# I2S_XLR_Adapter.net
KiCad netlist of a schematic drawn in EasyEDA Pro
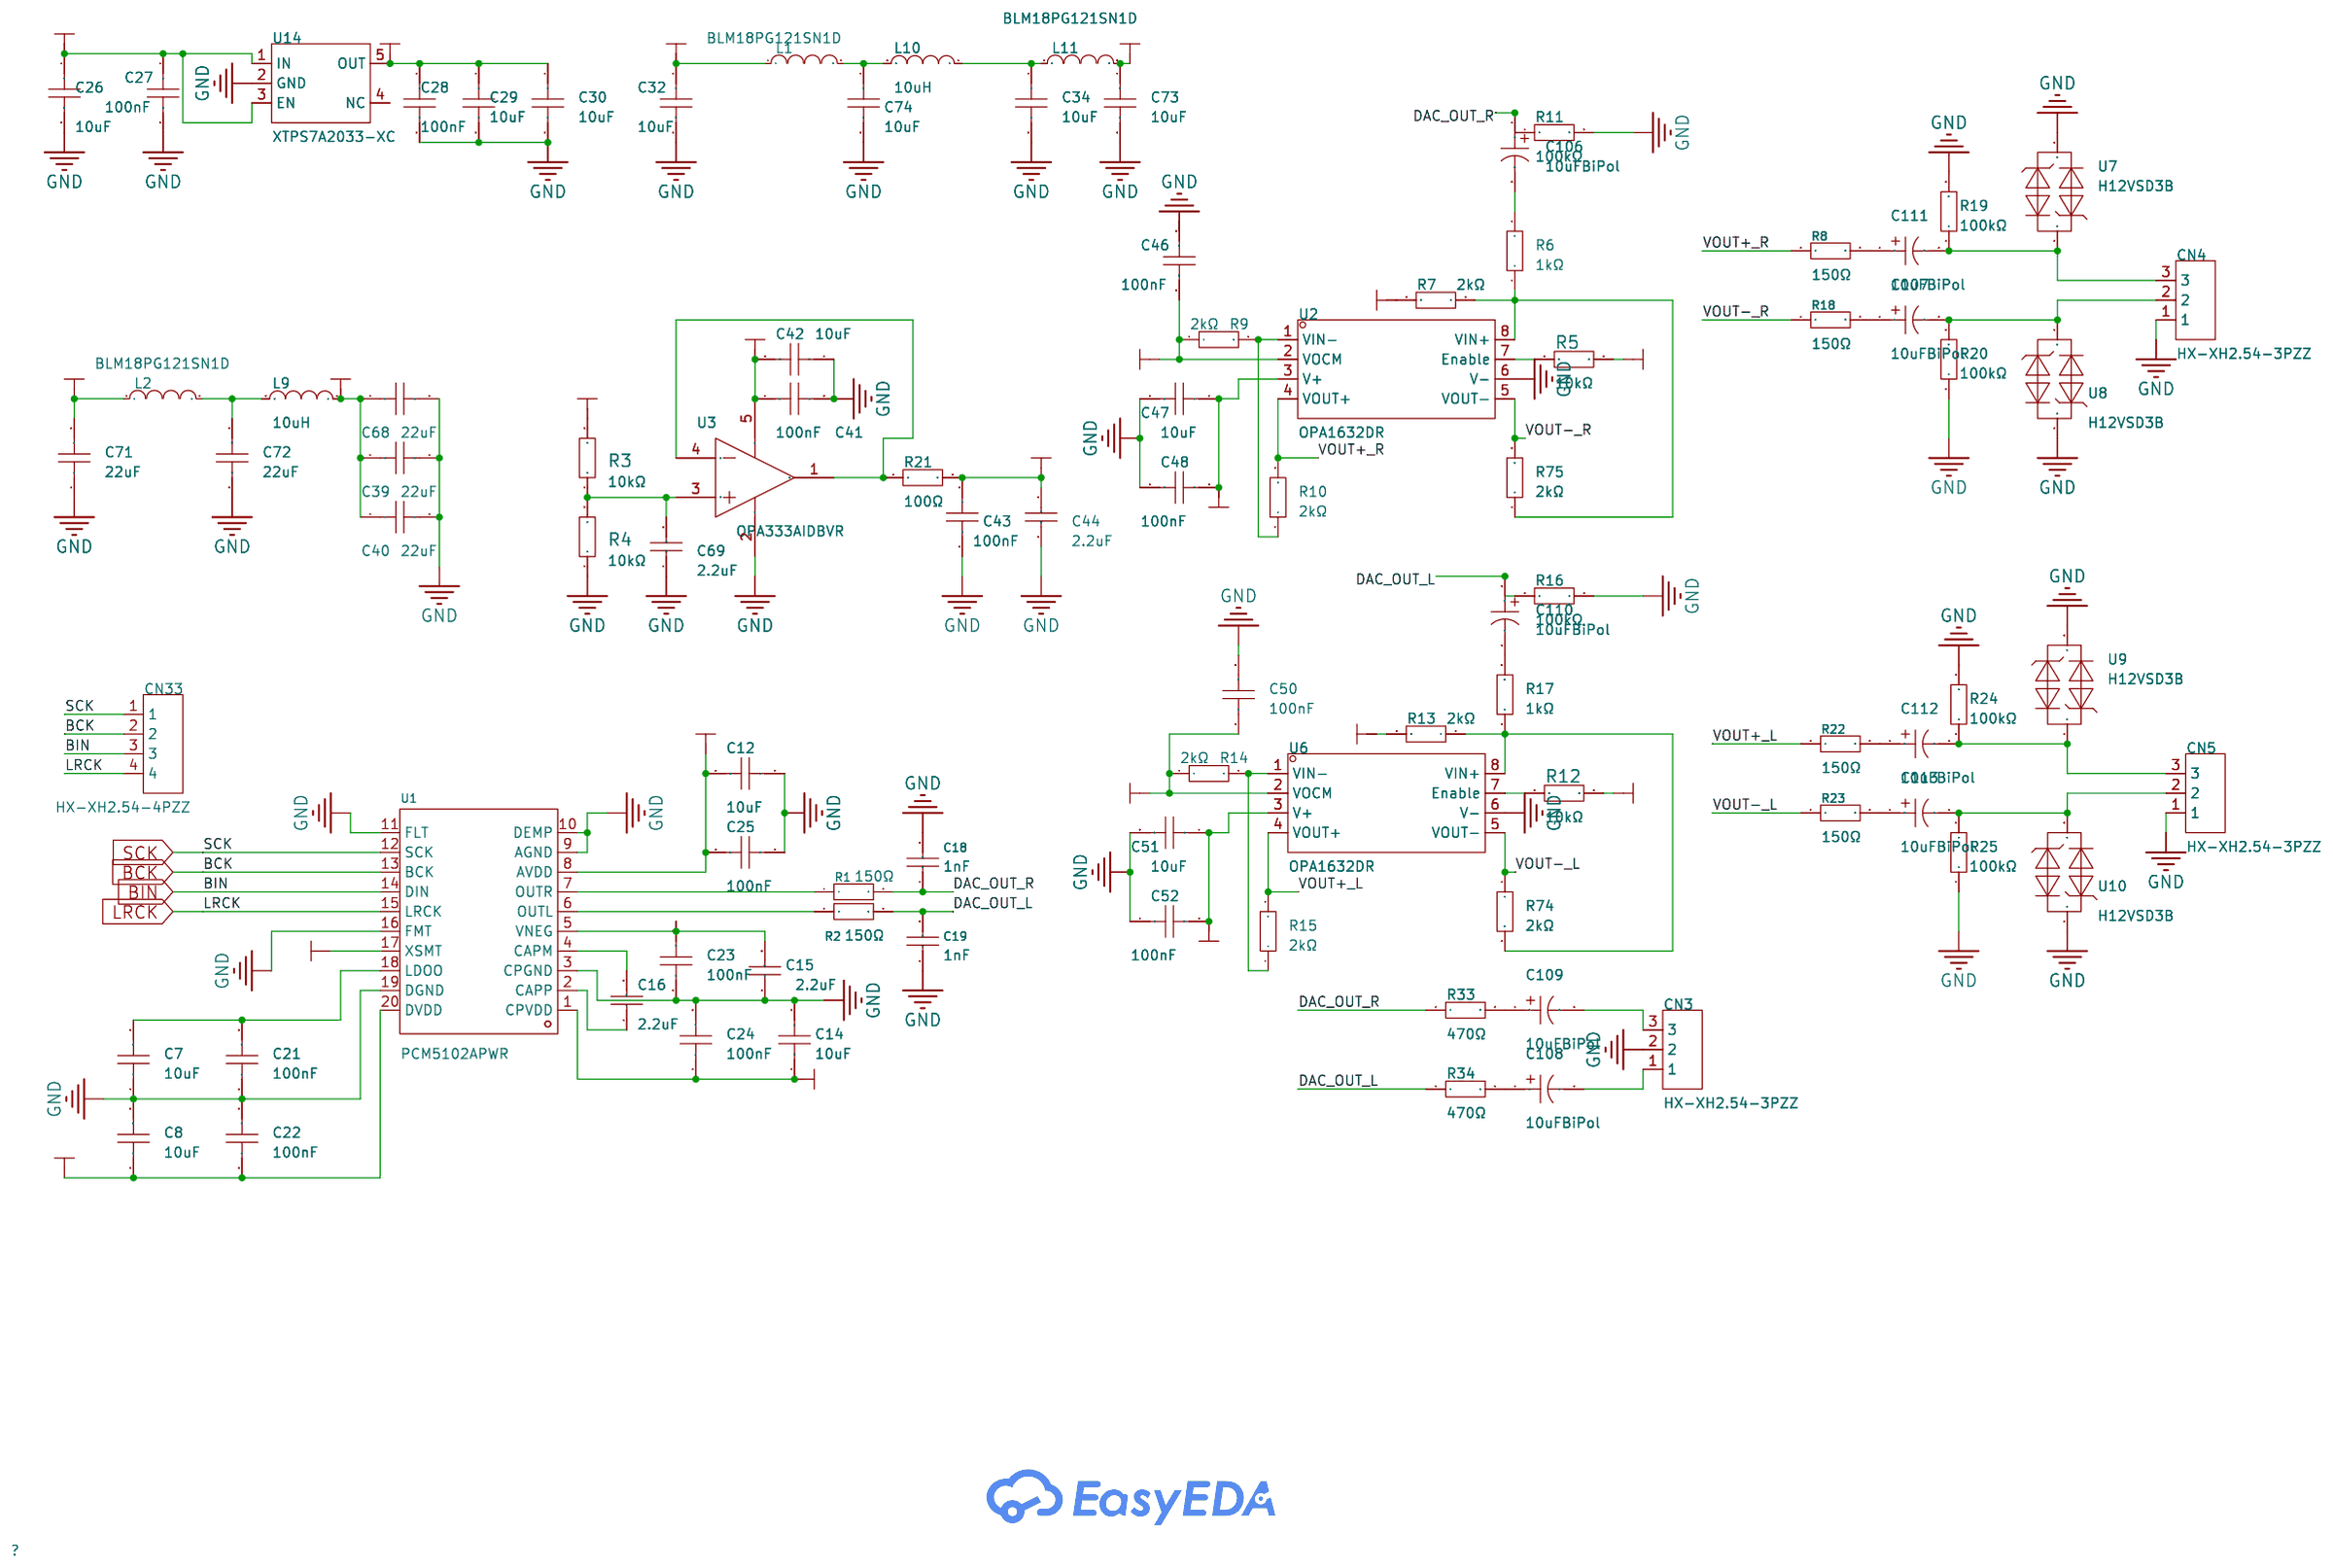
[diagram p0: DAC_XLR]
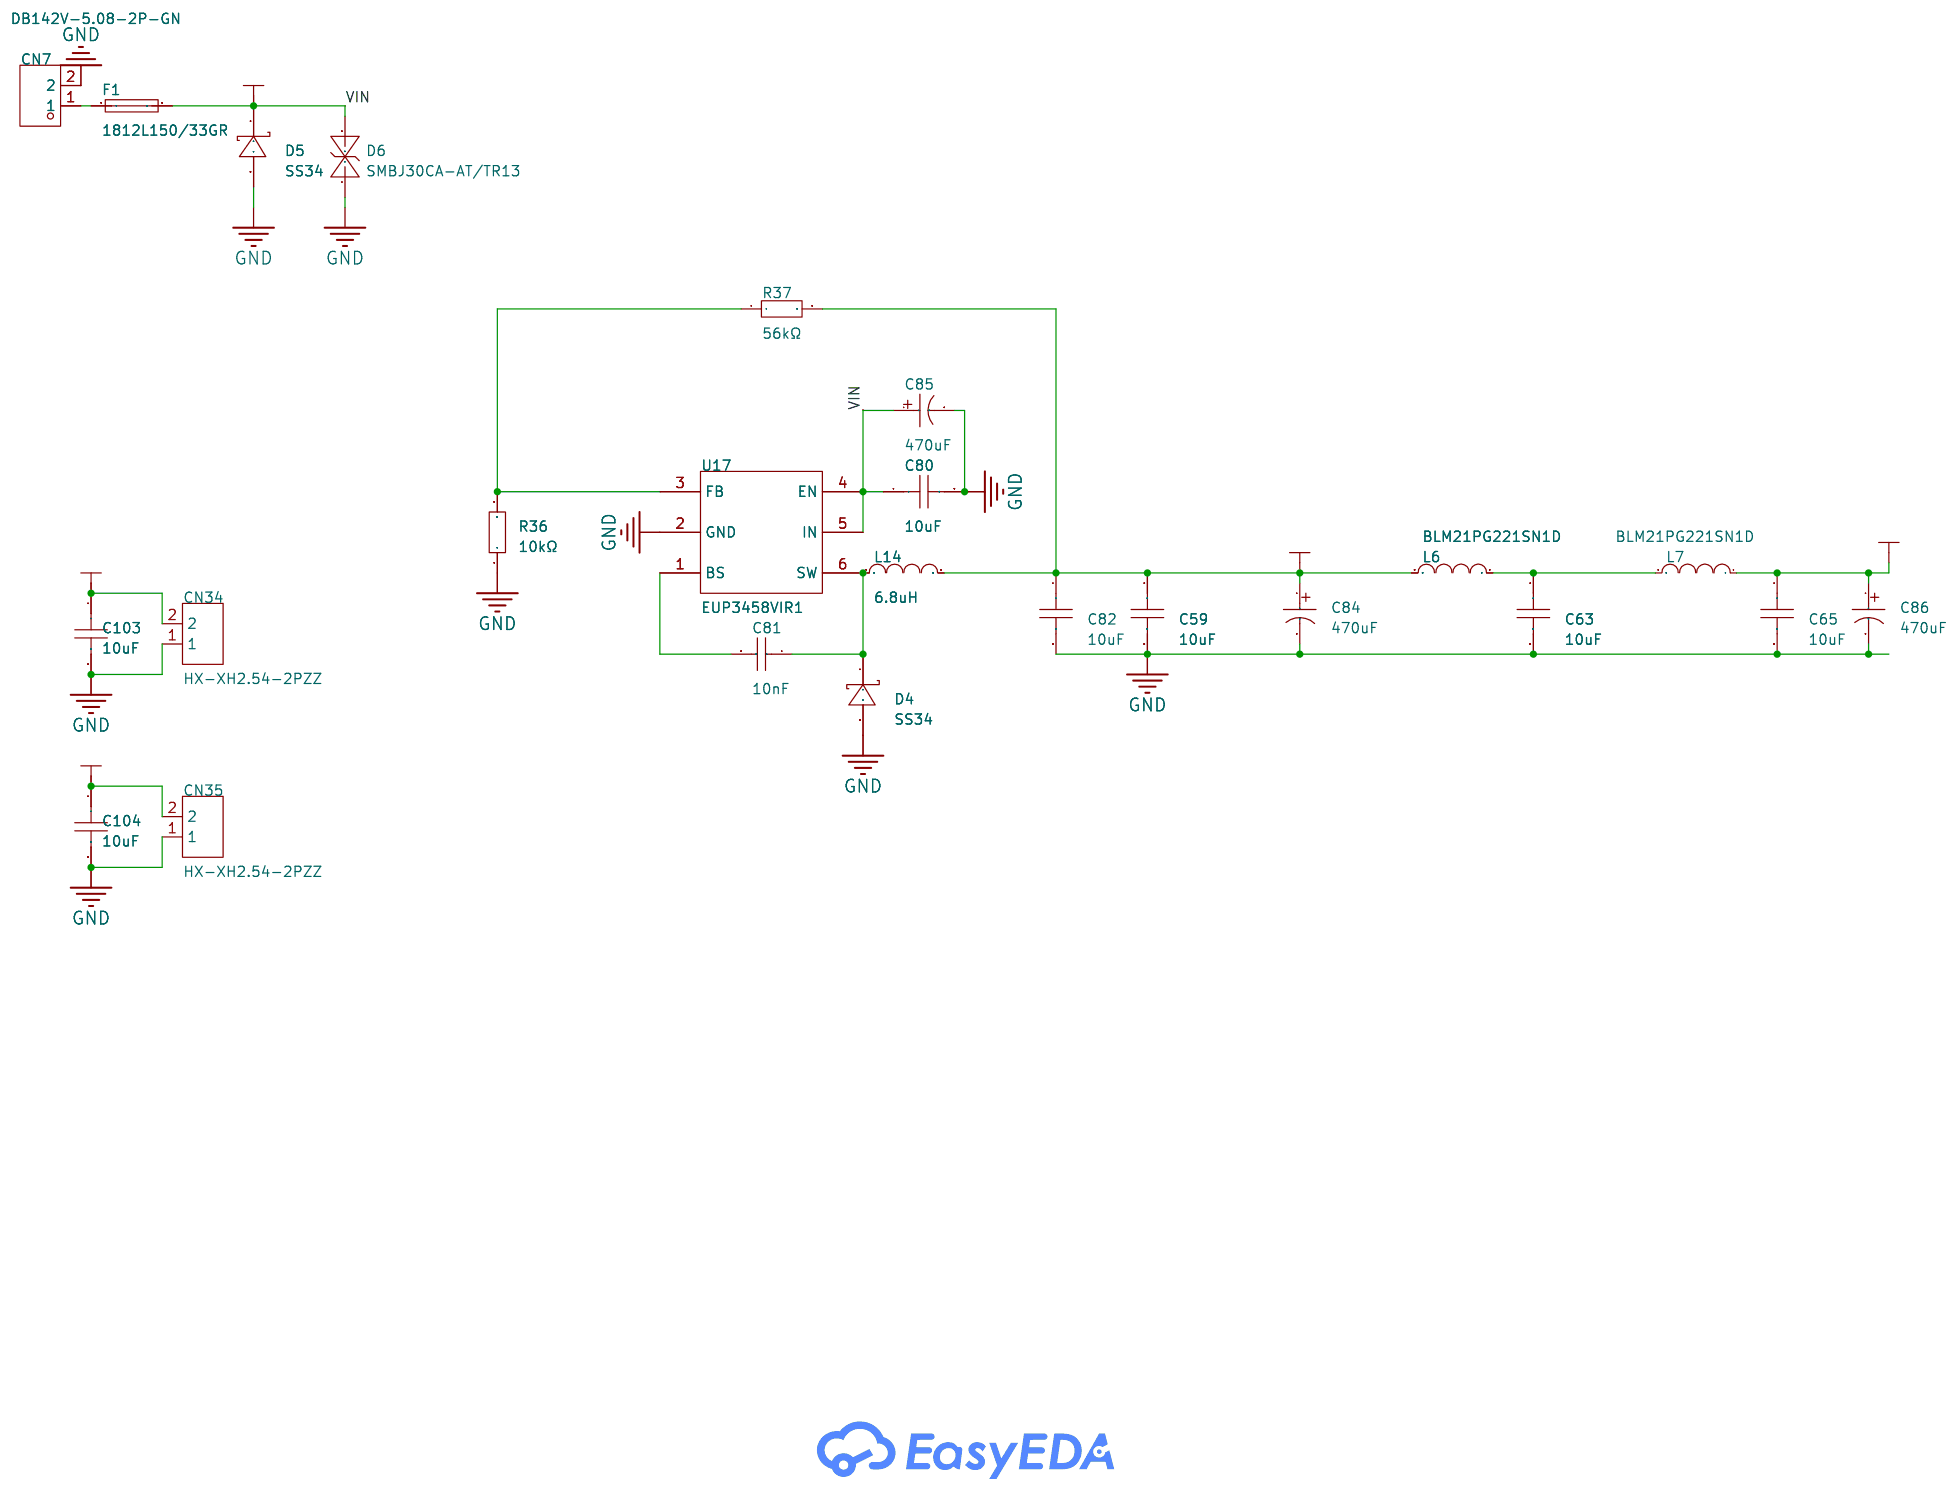
[diagram p1: Power]
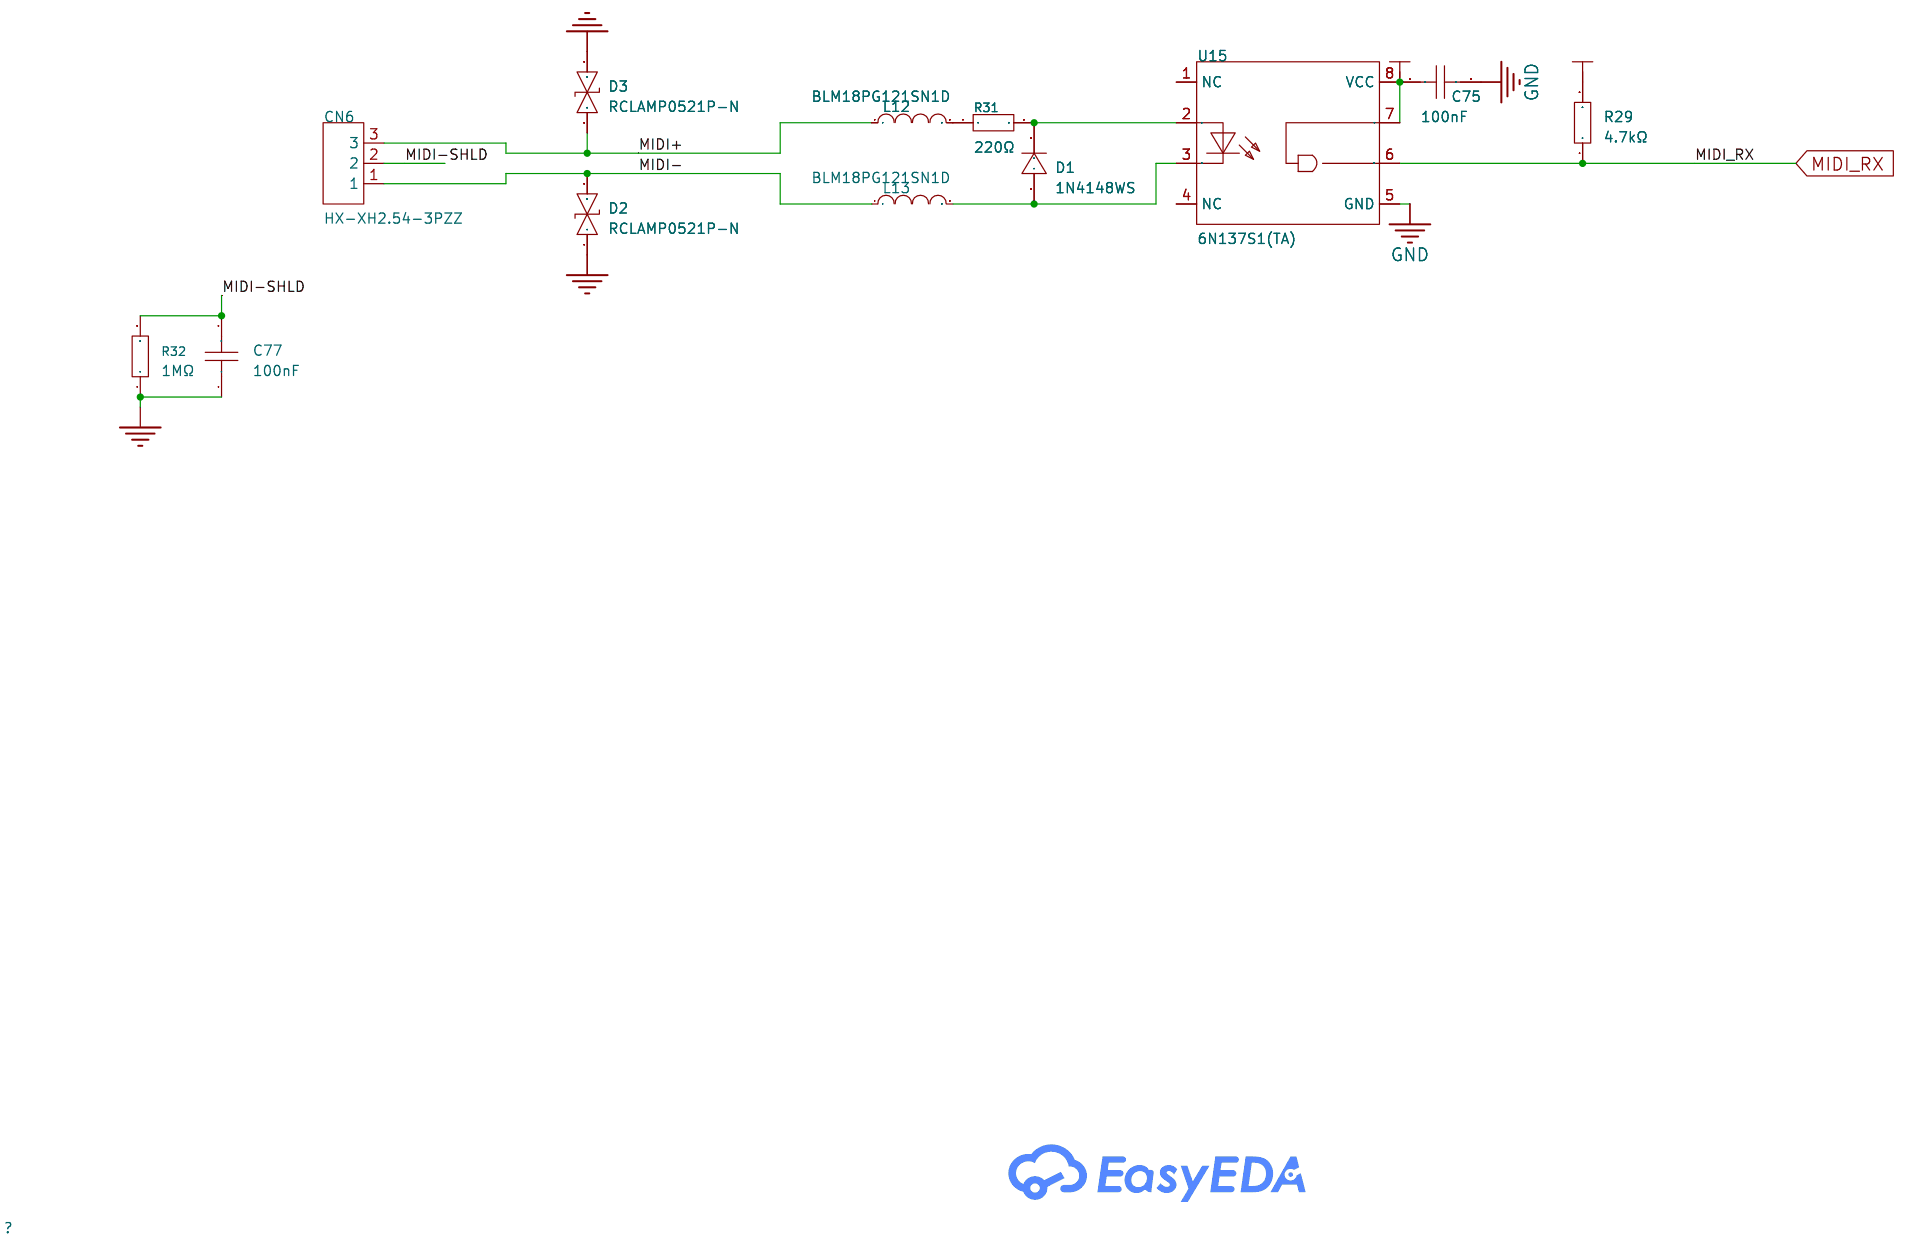
[diagram p2: MIDI]
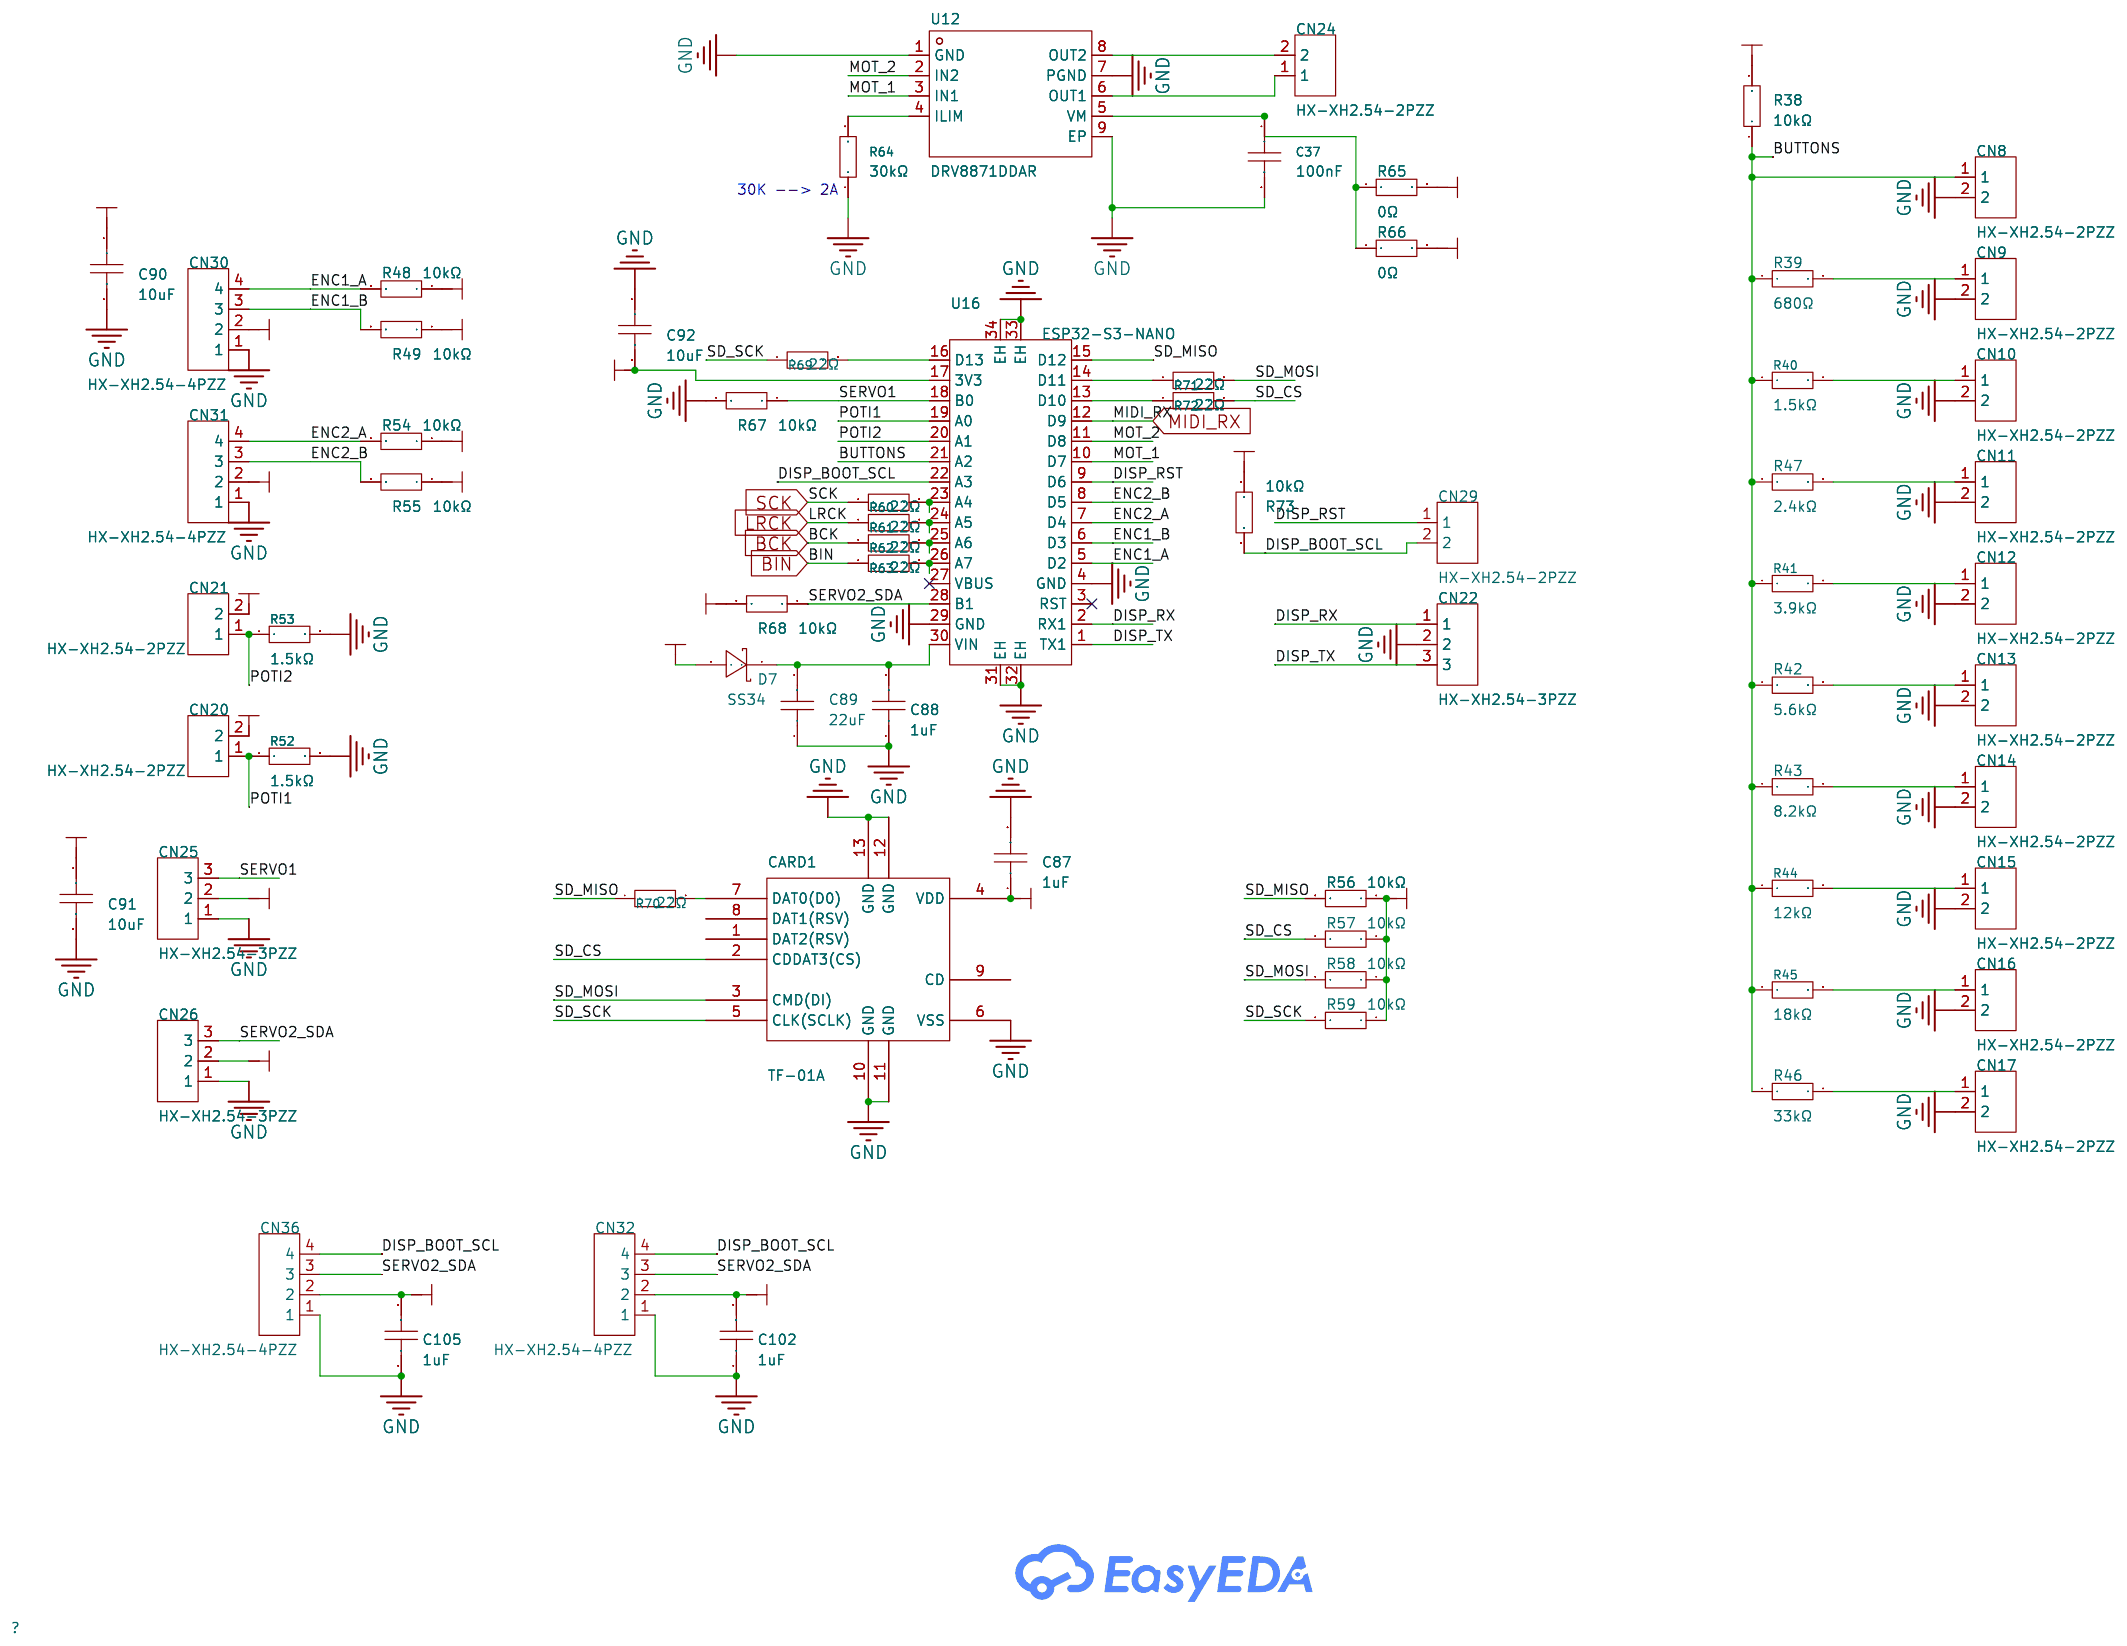
[diagram p3: ESP32]

(export (version "E")
  (design (tool "Eeschema 10.0.6"))
  (components
    (comp (ref "C7")
      (value "10uF")
      (footprint "easyedapro:C0805")
      (description "Capacitance:10uF Tolerance:±10% Tolerance:±10% Voltage Rating:25V Temperature Coefficient:X5R")
      (fields
        (field (name "Manufacturer Part") "CL21A106KAYNNNE")
        (field (name "Manufacturer") "SAMSUNG(三星)")
      )
      (libsource (lib "easyedapro") (part "CL21A106KAYNNNE"))
    )
    (comp (ref "C8")
      (value "10uF")
      (footprint "easyedapro:C0805")
      (description "Capacitance:10uF Tolerance:±10% Tolerance:±10% Voltage Rating:25V Temperature Coefficient:X5R")
      (fields
        (field (name "Manufacturer Part") "CL21A106KAYNNNE")
        (field (name "Manufacturer") "SAMSUNG(三星)")
      )
      (libsource (lib "easyedapro") (part "CL21A106KAYNNNE"))
    )
    (comp (ref "C12")
      (value "10uF")
      (footprint "easyedapro:C0805")
      (description "Capacitance:10uF Tolerance:±10% Tolerance:±10% Voltage Rating:25V Temperature Coefficient:X5R")
      (fields
        (field (name "Manufacturer Part") "CL21A106KAYNNNE")
        (field (name "Manufacturer") "SAMSUNG(三星)")
      )
      (libsource (lib "easyedapro") (part "CL21A106KAYNNNE"))
    )
    (comp (ref "C14")
      (value "10uF")
      (footprint "easyedapro:C0805")
      (description "Capacitance:10uF Tolerance:±10% Tolerance:±10% Voltage Rating:25V Temperature Coefficient:X5R")
      (fields
        (field (name "Manufacturer Part") "CL21A106KAYNNNE")
        (field (name "Manufacturer") "SAMSUNG(三星)")
      )
      (libsource (lib "easyedapro") (part "CL21A106KAYNNNE"))
    )
    (comp (ref "C15")
      (value "2.2uF")
      (footprint "easyedapro:C1206")
      (description "Capacitance:2.2uF Tolerance:±10% Tolerance:±10% Voltage Rating:50V Temperature Coefficient:X7R")
      (fields
        (field (name "Manufacturer Part") "CL31B225KBHNNNE")
        (field (name "Manufacturer") "SAMSUNG(三星)")
      )
      (libsource (lib "easyedapro") (part "CL31B225KBHNNNE"))
    )
    (comp (ref "C16")
      (value "2.2uF")
      (footprint "easyedapro:C1206")
      (description "Capacitance:2.2uF Tolerance:±10% Tolerance:±10% Voltage Rating:50V Temperature Coefficient:X7R")
      (fields
        (field (name "Manufacturer Part") "CL31B225KBHNNNE")
        (field (name "Manufacturer") "SAMSUNG(三星)")
      )
      (libsource (lib "easyedapro") (part "CL31B225KBHNNNE"))
    )
    (comp (ref "C18")
      (value "1nF")
      (footprint "easyedapro:C0603")
      (description "Capacitance:1nF Tolerance:±10% Tolerance:±10% Voltage Rating:50V Temperature Coefficient:X7R")
      (fields
        (field (name "Manufacturer Part") "CL10B102KB8NNNC")
        (field (name "Manufacturer") "SAMSUNG(三星)")
      )
      (libsource (lib "easyedapro") (part "CL10B102KB8NNNC"))
    )
    (comp (ref "C19")
      (value "1nF")
      (footprint "easyedapro:C0603")
      (description "Capacitance:1nF Tolerance:±10% Tolerance:±10% Voltage Rating:50V Temperature Coefficient:X7R")
      (fields
        (field (name "Manufacturer Part") "CL10B102KB8NNNC")
        (field (name "Manufacturer") "SAMSUNG(三星)")
      )
      (libsource (lib "easyedapro") (part "CL10B102KB8NNNC"))
    )
    (comp (ref "C21")
      (value "100nF")
      (footprint "easyedapro:C0402")
      (description "Capacitance:100nF Tolerance:±10% Tolerance:±10% Voltage Rating:50V Temperature Coefficient:X7R")
      (fields
        (field (name "Manufacturer Part") "CL05B104KB54PNC")
        (field (name "Manufacturer") "SAMSUNG(三星)")
      )
      (libsource (lib "easyedapro") (part "CL05B104KB54PNC"))
    )
    (comp (ref "C22")
      (value "100nF")
      (footprint "easyedapro:C0402")
      (description "Capacitance:100nF Tolerance:±10% Tolerance:±10% Voltage Rating:50V Temperature Coefficient:X7R")
      (fields
        (field (name "Manufacturer Part") "CL05B104KB54PNC")
        (field (name "Manufacturer") "SAMSUNG(三星)")
      )
      (libsource (lib "easyedapro") (part "CL05B104KB54PNC"))
    )
    (comp (ref "C23")
      (value "100nF")
      (footprint "easyedapro:C0402")
      (description "Capacitance:100nF Tolerance:±10% Tolerance:±10% Voltage Rating:50V Temperature Coefficient:X7R")
      (fields
        (field (name "Manufacturer Part") "CL05B104KB54PNC")
        (field (name "Manufacturer") "SAMSUNG(三星)")
      )
      (libsource (lib "easyedapro") (part "CL05B104KB54PNC"))
    )
    (comp (ref "C24")
      (value "100nF")
      (footprint "easyedapro:C0402")
      (description "Capacitance:100nF Tolerance:±10% Tolerance:±10% Voltage Rating:50V Temperature Coefficient:X7R")
      (fields
        (field (name "Manufacturer Part") "CL05B104KB54PNC")
        (field (name "Manufacturer") "SAMSUNG(三星)")
      )
      (libsource (lib "easyedapro") (part "CL05B104KB54PNC"))
    )
    (comp (ref "C25")
      (value "100nF")
      (footprint "easyedapro:C0402")
      (description "Capacitance:100nF Tolerance:±10% Tolerance:±10% Voltage Rating:50V Temperature Coefficient:X7R")
      (fields
        (field (name "Manufacturer Part") "CL05B104KB54PNC")
        (field (name "Manufacturer") "SAMSUNG(三星)")
      )
      (libsource (lib "easyedapro") (part "CL05B104KB54PNC"))
    )
    (comp (ref "C26")
      (value "10uF")
      (footprint "easyedapro:C0805")
      (description "Capacitance:10uF Tolerance:±10% Tolerance:±10% Voltage Rating:25V Temperature Coefficient:X5R")
      (fields
        (field (name "Manufacturer Part") "CL21A106KAYNNNE")
        (field (name "Manufacturer") "SAMSUNG(三星)")
      )
      (libsource (lib "easyedapro") (part "CL21A106KAYNNNE"))
    )
    (comp (ref "C27")
      (value "100nF")
      (footprint "easyedapro:C0402")
      (description "Capacitance:100nF Tolerance:±10% Tolerance:±10% Voltage Rating:50V Temperature Coefficient:X7R")
      (fields
        (field (name "Manufacturer Part") "CL05B104KB54PNC")
        (field (name "Manufacturer") "SAMSUNG(三星)")
      )
      (libsource (lib "easyedapro") (part "CL05B104KB54PNC"))
    )
    (comp (ref "C28")
      (value "100nF")
      (footprint "easyedapro:C0402")
      (description "Capacitance:100nF Tolerance:±10% Tolerance:±10% Voltage Rating:50V Temperature Coefficient:X7R")
      (fields
        (field (name "Manufacturer Part") "CL05B104KB54PNC")
        (field (name "Manufacturer") "SAMSUNG(三星)")
      )
      (libsource (lib "easyedapro") (part "CL05B104KB54PNC"))
    )
    (comp (ref "C29")
      (value "10uF")
      (footprint "easyedapro:C0805")
      (description "Capacitance:10uF Tolerance:±10% Tolerance:±10% Voltage Rating:25V Temperature Coefficient:X5R")
      (fields
        (field (name "Manufacturer Part") "CL21A106KAYNNNE")
        (field (name "Manufacturer") "SAMSUNG(三星)")
      )
      (libsource (lib "easyedapro") (part "CL21A106KAYNNNE"))
    )
    (comp (ref "C30")
      (value "10uF")
      (footprint "easyedapro:C0805")
      (description "Capacitance:10uF Tolerance:±10% Tolerance:±10% Voltage Rating:25V Temperature Coefficient:X5R")
      (fields
        (field (name "Manufacturer Part") "CL21A106KAYNNNE")
        (field (name "Manufacturer") "SAMSUNG(三星)")
      )
      (libsource (lib "easyedapro") (part "CL21A106KAYNNNE"))
    )
    (comp (ref "C32")
      (value "10uF")
      (footprint "easyedapro:C0805")
      (description "Capacitance:10uF Tolerance:±10% Tolerance:±10% Voltage Rating:25V Temperature Coefficient:X5R")
      (fields
        (field (name "Manufacturer Part") "CL21A106KAYNNNE")
        (field (name "Manufacturer") "SAMSUNG(三星)")
      )
      (libsource (lib "easyedapro") (part "CL21A106KAYNNNE"))
    )
    (comp (ref "C34")
      (value "10uF")
      (footprint "easyedapro:C0805")
      (description "Capacitance:10uF Tolerance:±10% Tolerance:±10% Voltage Rating:25V Temperature Coefficient:X5R")
      (fields
        (field (name "Manufacturer Part") "CL21A106KAYNNNE")
        (field (name "Manufacturer") "SAMSUNG(三星)")
      )
      (libsource (lib "easyedapro") (part "CL21A106KAYNNNE"))
    )
    (comp (ref "C39")
      (value "22uF")
      (footprint "easyedapro:C0805")
      (description "Capacitance:22uF Tolerance:±20% Tolerance:±20% Voltage Rating:25V Temperature Coefficient:X5R")
      (fields
        (field (name "Manufacturer Part") "CL21A226MAQNNNE")
        (field (name "Manufacturer") "SAMSUNG(三星)")
      )
      (libsource (lib "easyedapro") (part "CL21A226MAQNNNE"))
    )
    (comp (ref "C40")
      (value "22uF")
      (footprint "easyedapro:C0805")
      (description "Capacitance:22uF Tolerance:±20% Tolerance:±20% Voltage Rating:25V Temperature Coefficient:X5R")
      (fields
        (field (name "Manufacturer Part") "CL21A226MAQNNNE")
        (field (name "Manufacturer") "SAMSUNG(三星)")
      )
      (libsource (lib "easyedapro") (part "CL21A226MAQNNNE"))
    )
    (comp (ref "C41")
      (value "100nF")
      (footprint "easyedapro:C0402")
      (description "Capacitance:100nF Tolerance:±10% Tolerance:±10% Voltage Rating:50V Temperature Coefficient:X7R")
      (fields
        (field (name "Manufacturer Part") "CL05B104KB54PNC")
        (field (name "Manufacturer") "SAMSUNG(三星)")
      )
      (libsource (lib "easyedapro") (part "CL05B104KB54PNC"))
    )
    (comp (ref "C42")
      (value "10uF")
      (footprint "easyedapro:C0805")
      (description "Capacitance:10uF Tolerance:±10% Tolerance:±10% Voltage Rating:25V Temperature Coefficient:X5R")
      (fields
        (field (name "Manufacturer Part") "CL21A106KAYNNNE")
        (field (name "Manufacturer") "SAMSUNG(三星)")
      )
      (libsource (lib "easyedapro") (part "CL21A106KAYNNNE"))
    )
    (comp (ref "C43")
      (value "100nF")
      (footprint "easyedapro:C0402")
      (description "Capacitance:100nF Tolerance:±10% Tolerance:±10% Voltage Rating:50V Temperature Coefficient:X7R")
      (fields
        (field (name "Manufacturer Part") "CL05B104KB54PNC")
        (field (name "Manufacturer") "SAMSUNG(三星)")
      )
      (libsource (lib "easyedapro") (part "CL05B104KB54PNC"))
    )
    (comp (ref "C44")
      (value "2.2uF")
      (footprint "easyedapro:C1206")
      (description "Capacitance:2.2uF Tolerance:±10% Tolerance:±10% Voltage Rating:50V Temperature Coefficient:X7R")
      (fields
        (field (name "Manufacturer Part") "CL31B225KBHNNNE")
        (field (name "Manufacturer") "SAMSUNG(三星)")
      )
      (libsource (lib "easyedapro") (part "CL31B225KBHNNNE"))
    )
    (comp (ref "C46")
      (value "100nF")
      (footprint "easyedapro:C0402")
      (description "Capacitance:100nF Tolerance:±10% Tolerance:±10% Voltage Rating:50V Temperature Coefficient:X7R")
      (fields
        (field (name "Manufacturer Part") "CL05B104KB54PNC")
        (field (name "Manufacturer") "SAMSUNG(三星)")
      )
      (libsource (lib "easyedapro") (part "CL05B104KB54PNC"))
    )
    (comp (ref "C47")
      (value "10uF")
      (footprint "easyedapro:C0805")
      (description "Capacitance:10uF Tolerance:±10% Tolerance:±10% Voltage Rating:25V Temperature Coefficient:X5R")
      (fields
        (field (name "Manufacturer Part") "CL21A106KAYNNNE")
        (field (name "Manufacturer") "SAMSUNG(三星)")
      )
      (libsource (lib "easyedapro") (part "CL21A106KAYNNNE"))
    )
    (comp (ref "C48")
      (value "100nF")
      (footprint "easyedapro:C0402")
      (description "Capacitance:100nF Tolerance:±10% Tolerance:±10% Voltage Rating:50V Temperature Coefficient:X7R")
      (fields
        (field (name "Manufacturer Part") "CL05B104KB54PNC")
        (field (name "Manufacturer") "SAMSUNG(三星)")
      )
      (libsource (lib "easyedapro") (part "CL05B104KB54PNC"))
    )
    (comp (ref "C50")
      (value "100nF")
      (footprint "easyedapro:C0402")
      (description "Capacitance:100nF Tolerance:±10% Tolerance:±10% Voltage Rating:50V Temperature Coefficient:X7R")
      (fields
        (field (name "Manufacturer Part") "CL05B104KB54PNC")
        (field (name "Manufacturer") "SAMSUNG(三星)")
      )
      (libsource (lib "easyedapro") (part "CL05B104KB54PNC"))
    )
    (comp (ref "C51")
      (value "10uF")
      (footprint "easyedapro:C0805")
      (description "Capacitance:10uF Tolerance:±10% Tolerance:±10% Voltage Rating:25V Temperature Coefficient:X5R")
      (fields
        (field (name "Manufacturer Part") "CL21A106KAYNNNE")
        (field (name "Manufacturer") "SAMSUNG(三星)")
      )
      (libsource (lib "easyedapro") (part "CL21A106KAYNNNE"))
    )
    (comp (ref "C52")
      (value "100nF")
      (footprint "easyedapro:C0402")
      (description "Capacitance:100nF Tolerance:±10% Tolerance:±10% Voltage Rating:50V Temperature Coefficient:X7R")
      (fields
        (field (name "Manufacturer Part") "CL05B104KB54PNC")
        (field (name "Manufacturer") "SAMSUNG(三星)")
      )
      (libsource (lib "easyedapro") (part "CL05B104KB54PNC"))
    )
    (comp (ref "C68")
      (value "22uF")
      (footprint "easyedapro:C0805")
      (description "Capacitance:22uF Tolerance:±20% Tolerance:±20% Voltage Rating:25V Temperature Coefficient:X5R")
      (fields
        (field (name "Manufacturer Part") "CL21A226MAQNNNE")
        (field (name "Manufacturer") "SAMSUNG(三星)")
      )
      (libsource (lib "easyedapro") (part "CL21A226MAQNNNE"))
    )
    (comp (ref "C69")
      (value "2.2uF")
      (footprint "easyedapro:C1206")
      (description "Capacitance:2.2uF Tolerance:±10% Tolerance:±10% Voltage Rating:50V Temperature Coefficient:X7R")
      (fields
        (field (name "Manufacturer Part") "CL31B225KBHNNNE")
        (field (name "Manufacturer") "SAMSUNG(三星)")
      )
      (libsource (lib "easyedapro") (part "CL31B225KBHNNNE"))
    )
    (comp (ref "C71")
      (value "22uF")
      (footprint "easyedapro:C0805")
      (description "Capacitance:22uF Tolerance:±20% Tolerance:±20% Voltage Rating:25V Temperature Coefficient:X5R")
      (fields
        (field (name "Manufacturer Part") "CL21A226MAQNNNE")
        (field (name "Manufacturer") "SAMSUNG(三星)")
      )
      (libsource (lib "easyedapro") (part "CL21A226MAQNNNE"))
    )
    (comp (ref "C72")
      (value "22uF")
      (footprint "easyedapro:C0805")
      (description "Capacitance:22uF Tolerance:±20% Tolerance:±20% Voltage Rating:25V Temperature Coefficient:X5R")
      (fields
        (field (name "Manufacturer Part") "CL21A226MAQNNNE")
        (field (name "Manufacturer") "SAMSUNG(三星)")
      )
      (libsource (lib "easyedapro") (part "CL21A226MAQNNNE"))
    )
    (comp (ref "C73")
      (value "10uF")
      (footprint "easyedapro:C0805")
      (description "Capacitance:10uF Tolerance:±10% Tolerance:±10% Voltage Rating:25V Temperature Coefficient:X5R")
      (fields
        (field (name "Manufacturer Part") "CL21A106KAYNNNE")
        (field (name "Manufacturer") "SAMSUNG(三星)")
      )
      (libsource (lib "easyedapro") (part "CL21A106KAYNNNE"))
    )
    (comp (ref "C74")
      (value "10uF")
      (footprint "easyedapro:C0805")
      (description "Capacitance:10uF Tolerance:±10% Tolerance:±10% Voltage Rating:25V Temperature Coefficient:X5R")
      (fields
        (field (name "Manufacturer Part") "CL21A106KAYNNNE")
        (field (name "Manufacturer") "SAMSUNG(三星)")
      )
      (libsource (lib "easyedapro") (part "CL21A106KAYNNNE"))
    )
    (comp (ref "C106")
      (value "10uFBiPol")
      (footprint "easyedapro:CAP-TH_BD8.0-P3.50-D0.6-FD_1")
      (fields (field (name "Manufacturer Part") "UES1C470MPM") (field (name "Manufacturer") "Nichicon(尼吉康)"))
      (libsource (lib "easyedapro") (part "UES1C470MPM"))
    )
    (comp (ref "C107")
      (value "10uFBiPol")
      (footprint "easyedapro:CAP-TH_BD8.0-P3.50-D0.6-FD_1")
      (fields (field (name "Manufacturer Part") "UES1C470MPM") (field (name "Manufacturer") "Nichicon(尼吉康)"))
      (libsource (lib "easyedapro") (part "UES1C470MPM"))
    )
    (comp (ref "C108")
      (value "10uFBiPol")
      (footprint "easyedapro:CAP-TH_BD8.0-P3.50-D0.6-FD_1")
      (fields (field (name "Manufacturer Part") "UES1C470MPM") (field (name "Manufacturer") "Nichicon(尼吉康)"))
      (libsource (lib "easyedapro") (part "UES1C470MPM"))
    )
    (comp (ref "C109")
      (value "10uFBiPol")
      (footprint "easyedapro:CAP-TH_BD8.0-P3.50-D0.6-FD_1")
      (fields (field (name "Manufacturer Part") "UES1C470MPM") (field (name "Manufacturer") "Nichicon(尼吉康)"))
      (libsource (lib "easyedapro") (part "UES1C470MPM"))
    )
    (comp (ref "C110")
      (value "10uFBiPol")
      (footprint "easyedapro:CAP-TH_BD8.0-P3.50-D0.6-FD_1")
      (fields (field (name "Manufacturer Part") "UES1C470MPM") (field (name "Manufacturer") "Nichicon(尼吉康)"))
      (libsource (lib "easyedapro") (part "UES1C470MPM"))
    )
    (comp (ref "C111")
      (value "10uFBiPol")
      (footprint "easyedapro:CAP-TH_BD8.0-P3.50-D0.6-FD_1")
      (fields (field (name "Manufacturer Part") "UES1C470MPM") (field (name "Manufacturer") "Nichicon(尼吉康)"))
      (libsource (lib "easyedapro") (part "UES1C470MPM"))
    )
    (comp (ref "C112")
      (value "10uFBiPol")
      (footprint "easyedapro:CAP-TH_BD8.0-P3.50-D0.6-FD_1")
      (fields (field (name "Manufacturer Part") "UES1C470MPM") (field (name "Manufacturer") "Nichicon(尼吉康)"))
      (libsource (lib "easyedapro") (part "UES1C470MPM"))
    )
    (comp (ref "C113")
      (value "10uFBiPol")
      (footprint "easyedapro:CAP-TH_BD8.0-P3.50-D0.6-FD_1")
      (fields (field (name "Manufacturer Part") "UES1C470MPM") (field (name "Manufacturer") "Nichicon(尼吉康)"))
      (libsource (lib "easyedapro") (part "UES1C470MPM"))
    )
    (comp (ref "CN3")
      (value "HX-XH2.54-3PZZ")
      (footprint "easyedapro:CONN-TH_3P-P2.50_HC-XH-3A-G")
      (fields (field (name "Manufacturer") "hanxia(韩下)"))
      (libsource (lib "easyedapro") (part "HX-XH2.54-3PZZ"))
    )
    (comp (ref "CN4")
      (value "HX-XH2.54-3PZZ")
      (footprint "easyedapro:CONN-TH_3P-P2.50_HC-XH-3A-G")
      (fields (field (name "Manufacturer") "hanxia(韩下)"))
      (libsource (lib "easyedapro") (part "HX-XH2.54-3PZZ"))
    )
    (comp (ref "CN5")
      (value "HX-XH2.54-3PZZ")
      (footprint "easyedapro:CONN-TH_3P-P2.50_HC-XH-3A-G")
      (fields (field (name "Manufacturer") "hanxia(韩下)"))
      (libsource (lib "easyedapro") (part "HX-XH2.54-3PZZ"))
    )
    (comp (ref "CN33")
      (value "HX-XH2.54-4PZZ")
      (footprint "easyedapro:CONN-TH_4P-P2.50-XH2.54-4P")
      (fields (field (name "Manufacturer") "hanxia(韩下)"))
      (libsource (lib "easyedapro") (part "HX-XH2.54-4PZZ"))
    )
    (comp (ref "L1")
      (value "BLM18PG121SN1D")
      (footprint "easyedapro:L0603")
      (fields (field (name "Manufacturer") "muRata(村田)"))
      (libsource (lib "easyedapro") (part "BLM18PG121SN1D_C14709"))
    )
    (comp (ref "L2")
      (value "BLM18PG121SN1D")
      (footprint "easyedapro:L0603")
      (fields (field (name "Manufacturer") "muRata(村田)"))
      (libsource (lib "easyedapro") (part "BLM18PG121SN1D_C14709"))
    )
    (comp (ref "L9")
      (value "10uH")
      (footprint "easyedapro:IND-SMD_L2.5-W2.0")
      (fields
        (field (name "Manufacturer Part") "FTC252012S100MBCA")
        (field (name "Manufacturer") "cjiang(长江微电)")
      )
      (libsource (lib "easyedapro") (part "FTC252012S100MBCA"))
    )
    (comp (ref "L10")
      (value "10uH")
      (footprint "easyedapro:IND-SMD_L2.5-W2.0")
      (fields
        (field (name "Manufacturer Part") "FTC252012S100MBCA")
        (field (name "Manufacturer") "cjiang(长江微电)")
      )
      (libsource (lib "easyedapro") (part "FTC252012S100MBCA"))
    )
    (comp (ref "L11")
      (value "BLM18PG121SN1D")
      (footprint "easyedapro:L0603")
      (fields (field (name "Manufacturer") "muRata(村田)"))
      (libsource (lib "easyedapro") (part "BLM18PG121SN1D_C14709"))
    )
    (comp (ref "R1")
      (value "150Ω")
      (footprint "easyedapro:R0603")
      (fields
        (field (name "Manufacturer Part") "0603WAF1500T5E")
        (field (name "Manufacturer") "UNI-ROYAL(厚声)")
      )
      (libsource (lib "easyedapro") (part "0603WAF1500T5E"))
    )
    (comp (ref "R2")
      (value "150Ω")
      (footprint "easyedapro:R0603")
      (fields
        (field (name "Manufacturer Part") "0603WAF1500T5E")
        (field (name "Manufacturer") "UNI-ROYAL(厚声)")
      )
      (libsource (lib "easyedapro") (part "0603WAF1500T5E"))
    )
    (comp (ref "R3")
      (value "10kΩ")
      (footprint "easyedapro:R0603")
      (fields
        (field (name "Manufacturer Part") "0603WAF1002T5E")
        (field (name "Manufacturer") "UNI-ROYAL(厚声)")
      )
      (libsource (lib "easyedapro") (part "0603WAF1002T5E"))
    )
    (comp (ref "R4")
      (value "10kΩ")
      (footprint "easyedapro:R0603")
      (fields
        (field (name "Manufacturer Part") "0603WAF1002T5E")
        (field (name "Manufacturer") "UNI-ROYAL(厚声)")
      )
      (libsource (lib "easyedapro") (part "0603WAF1002T5E"))
    )
    (comp (ref "R5")
      (value "10kΩ")
      (footprint "easyedapro:R0603")
      (fields
        (field (name "Manufacturer Part") "0603WAF1002T5E")
        (field (name "Manufacturer") "UNI-ROYAL(厚声)")
      )
      (libsource (lib "easyedapro") (part "0603WAF1002T5E"))
    )
    (comp (ref "R6")
      (value "1kΩ")
      (footprint "easyedapro:R0603")
      (fields
        (field (name "Manufacturer Part") "0603WAF1001T5E")
        (field (name "Manufacturer") "UNI-ROYAL(厚声)")
      )
      (libsource (lib "easyedapro") (part "0603WAF1001T5E"))
    )
    (comp (ref "R7")
      (value "2kΩ")
      (footprint "easyedapro:R0603")
      (fields
        (field (name "Manufacturer Part") "0603WAF2001T5E")
        (field (name "Manufacturer") "UNI-ROYAL(厚声)")
      )
      (libsource (lib "easyedapro") (part "0603WAF2001T5E"))
    )
    (comp (ref "R8")
      (value "150Ω")
      (footprint "easyedapro:R0603")
      (fields
        (field (name "Manufacturer Part") "0603WAF1500T5E")
        (field (name "Manufacturer") "UNI-ROYAL(厚声)")
      )
      (libsource (lib "easyedapro") (part "0603WAF1500T5E"))
    )
    (comp (ref "R9")
      (value "2kΩ")
      (footprint "easyedapro:R0603")
      (fields
        (field (name "Manufacturer Part") "0603WAF2001T5E")
        (field (name "Manufacturer") "UNI-ROYAL(厚声)")
      )
      (libsource (lib "easyedapro") (part "0603WAF2001T5E"))
    )
    (comp (ref "R10")
      (value "2kΩ")
      (footprint "easyedapro:R0603")
      (fields
        (field (name "Manufacturer Part") "0603WAF2001T5E")
        (field (name "Manufacturer") "UNI-ROYAL(厚声)")
      )
      (libsource (lib "easyedapro") (part "0603WAF2001T5E"))
    )
    (comp (ref "R11")
      (value "100kΩ")
      (footprint "easyedapro:R0603")
      (fields
        (field (name "Manufacturer Part") "0603WAF1003T5E")
        (field (name "Manufacturer") "UNI-ROYAL(厚声)")
      )
      (libsource (lib "easyedapro") (part "0603WAF1003T5E"))
    )
    (comp (ref "R12")
      (value "10kΩ")
      (footprint "easyedapro:R0603")
      (fields
        (field (name "Manufacturer Part") "0603WAF1002T5E")
        (field (name "Manufacturer") "UNI-ROYAL(厚声)")
      )
      (libsource (lib "easyedapro") (part "0603WAF1002T5E"))
    )
    (comp (ref "R13")
      (value "2kΩ")
      (footprint "easyedapro:R0603")
      (fields
        (field (name "Manufacturer Part") "0603WAF2001T5E")
        (field (name "Manufacturer") "UNI-ROYAL(厚声)")
      )
      (libsource (lib "easyedapro") (part "0603WAF2001T5E"))
    )
    (comp (ref "R14")
      (value "2kΩ")
      (footprint "easyedapro:R0603")
      (fields
        (field (name "Manufacturer Part") "0603WAF2001T5E")
        (field (name "Manufacturer") "UNI-ROYAL(厚声)")
      )
      (libsource (lib "easyedapro") (part "0603WAF2001T5E"))
    )
    (comp (ref "R15")
      (value "2kΩ")
      (footprint "easyedapro:R0603")
      (fields
        (field (name "Manufacturer Part") "0603WAF2001T5E")
        (field (name "Manufacturer") "UNI-ROYAL(厚声)")
      )
      (libsource (lib "easyedapro") (part "0603WAF2001T5E"))
    )
    (comp (ref "R16")
      (value "100kΩ")
      (footprint "easyedapro:R0603")
      (fields
        (field (name "Manufacturer Part") "0603WAF1003T5E")
        (field (name "Manufacturer") "UNI-ROYAL(厚声)")
      )
      (libsource (lib "easyedapro") (part "0603WAF1003T5E"))
    )
    (comp (ref "R17")
      (value "1kΩ")
      (footprint "easyedapro:R0603")
      (fields
        (field (name "Manufacturer Part") "0603WAF1001T5E")
        (field (name "Manufacturer") "UNI-ROYAL(厚声)")
      )
      (libsource (lib "easyedapro") (part "0603WAF1001T5E"))
    )
    (comp (ref "R18")
      (value "150Ω")
      (footprint "easyedapro:R0603")
      (fields
        (field (name "Manufacturer Part") "0603WAF1500T5E")
        (field (name "Manufacturer") "UNI-ROYAL(厚声)")
      )
      (libsource (lib "easyedapro") (part "0603WAF1500T5E"))
    )
    (comp (ref "R19")
      (value "100kΩ")
      (footprint "easyedapro:R0603")
      (fields
        (field (name "Manufacturer Part") "0603WAF1003T5E")
        (field (name "Manufacturer") "UNI-ROYAL(厚声)")
      )
      (libsource (lib "easyedapro") (part "0603WAF1003T5E"))
    )
    (comp (ref "R20")
      (value "100kΩ")
      (footprint "easyedapro:R0603")
      (fields
        (field (name "Manufacturer Part") "0603WAF1003T5E")
        (field (name "Manufacturer") "UNI-ROYAL(厚声)")
      )
      (libsource (lib "easyedapro") (part "0603WAF1003T5E"))
    )
    (comp (ref "R21")
      (value "100Ω")
      (footprint "easyedapro:R0402")
      (fields
        (field (name "Manufacturer Part") "0402WGF1000TCE")
        (field (name "Manufacturer") "UNI-ROYAL(厚声)")
      )
      (libsource (lib "easyedapro") (part "0402WGF1000TCE"))
    )
    (comp (ref "R22")
      (value "150Ω")
      (footprint "easyedapro:R0603")
      (fields
        (field (name "Manufacturer Part") "0603WAF1500T5E")
        (field (name "Manufacturer") "UNI-ROYAL(厚声)")
      )
      (libsource (lib "easyedapro") (part "0603WAF1500T5E"))
    )
    (comp (ref "R23")
      (value "150Ω")
      (footprint "easyedapro:R0603")
      (fields
        (field (name "Manufacturer Part") "0603WAF1500T5E")
        (field (name "Manufacturer") "UNI-ROYAL(厚声)")
      )
      (libsource (lib "easyedapro") (part "0603WAF1500T5E"))
    )
    (comp (ref "R24")
      (value "100kΩ")
      (footprint "easyedapro:R0603")
      (fields
        (field (name "Manufacturer Part") "0603WAF1003T5E")
        (field (name "Manufacturer") "UNI-ROYAL(厚声)")
      )
      (libsource (lib "easyedapro") (part "0603WAF1003T5E"))
    )
    (comp (ref "R25")
      (value "100kΩ")
      (footprint "easyedapro:R0603")
      (fields
        (field (name "Manufacturer Part") "0603WAF1003T5E")
        (field (name "Manufacturer") "UNI-ROYAL(厚声)")
      )
      (libsource (lib "easyedapro") (part "0603WAF1003T5E"))
    )
    (comp (ref "R33")
      (value "470Ω")
      (footprint "easyedapro:R0603")
      (fields
        (field (name "Manufacturer Part") "0603WAF4700T5E")
        (field (name "Manufacturer") "UNI-ROYAL(厚声)")
      )
      (libsource (lib "easyedapro") (part "0603WAF4700T5E"))
    )
    (comp (ref "R34")
      (value "470Ω")
      (footprint "easyedapro:R0603")
      (fields
        (field (name "Manufacturer Part") "0603WAF4700T5E")
        (field (name "Manufacturer") "UNI-ROYAL(厚声)")
      )
      (libsource (lib "easyedapro") (part "0603WAF4700T5E"))
    )
    (comp (ref "R74")
      (value "2kΩ")
      (footprint "easyedapro:R0603")
      (fields
        (field (name "Manufacturer Part") "0603WAF2001T5E")
        (field (name "Manufacturer") "UNI-ROYAL(厚声)")
      )
      (libsource (lib "easyedapro") (part "0603WAF2001T5E"))
    )
    (comp (ref "R75")
      (value "2kΩ")
      (footprint "easyedapro:R0603")
      (fields
        (field (name "Manufacturer Part") "0603WAF2001T5E")
        (field (name "Manufacturer") "UNI-ROYAL(厚声)")
      )
      (libsource (lib "easyedapro") (part "0603WAF2001T5E"))
    )
    (comp (ref "U1")
      (value "PCM5102APWR")
      (footprint "easyedapro:TSSOP-20_L6.5-W4.4-P0.65-LS6.4-BL")
      (fields (field (name "Manufacturer") "TI(德州仪器)"))
      (libsource (lib "easyedapro") (part "PCM5102APWR"))
    )
    (comp (ref "U2")
      (value "OPA1632DR")
      (footprint "easyedapro:SOIC-8_L4.9-W3.9-P1.27-LS6.0-BL")
      (description "Speaker Channels:1-Channel Operating Temperature:-40°C~+85°C Operating Temperature:-40°C~+85°C")
      (fields (field (name "Manufacturer") "TI(德州仪器)"))
      (libsource (lib "easyedapro") (part "OPA1632D"))
    )
    (comp (ref "U3")
      (value "OPA333AIDBVR")
      (footprint "easyedapro:SOT-23-5_L3.0-W1.7-P0.95-LS2.8-BR")
      (fields (field (name "Manufacturer") "TI(德州仪器)"))
      (libsource (lib "easyedapro") (part "OPA333AIDBVR"))
    )
    (comp (ref "U6")
      (value "OPA1632DR")
      (footprint "easyedapro:SOIC-8_L4.9-W3.9-P1.27-LS6.0-BL")
      (description "Speaker Channels:1-Channel Operating Temperature:-40°C~+85°C Operating Temperature:-40°C~+85°C")
      (fields (field (name "Manufacturer") "TI(德州仪器)"))
      (libsource (lib "easyedapro") (part "OPA1632D"))
    )
    (comp (ref "U7")
      (value "H12VSD3B")
      (footprint "easyedapro:SOD-323_L1.8-W1.3-LS2.7-BI")
      (fields (field (name "Manufacturer") "R+O(宏嘉诚)"))
      (libsource (lib "easyedapro") (part "H12VSD3B"))
    )
    (comp (ref "U8")
      (value "H12VSD3B")
      (footprint "easyedapro:SOD-323_L1.8-W1.3-LS2.7-BI")
      (fields (field (name "Manufacturer") "R+O(宏嘉诚)"))
      (libsource (lib "easyedapro") (part "H12VSD3B"))
    )
    (comp (ref "U9")
      (value "H12VSD3B")
      (footprint "easyedapro:SOD-323_L1.8-W1.3-LS2.7-BI")
      (fields (field (name "Manufacturer") "R+O(宏嘉诚)"))
      (libsource (lib "easyedapro") (part "H12VSD3B"))
    )
    (comp (ref "U10")
      (value "H12VSD3B")
      (footprint "easyedapro:SOD-323_L1.8-W1.3-LS2.7-BI")
      (fields (field (name "Manufacturer") "R+O(宏嘉诚)"))
      (libsource (lib "easyedapro") (part "H12VSD3B"))
    )
    (comp (ref "U14")
      (value "XTPS7A2033-XC")
      (footprint "easyedapro:SOT-23-5_L3.0-W1.7-P0.95-LS2.8-BL")
      (fields (field (name "Manufacturer") "SiChange(芯昌科技)"))
      (libsource (lib "easyedapro") (part "XTPS7A2033"))
    )
    (comp (ref "C59")
      (value "10uF")
      (footprint "easyedapro:C0805")
      (description "Capacitance:10uF Tolerance:±10% Tolerance:±10% Voltage Rating:25V Temperature Coefficient:X5R")
      (fields
        (field (name "Manufacturer Part") "CL21A106KAYNNNE")
        (field (name "Manufacturer") "SAMSUNG(三星)")
      )
      (libsource (lib "easyedapro") (part "CL21A106KAYNNNE"))
    )
    (comp (ref "C63")
      (value "10uF")
      (footprint "easyedapro:C0805")
      (description "Capacitance:10uF Tolerance:±10% Tolerance:±10% Voltage Rating:25V Temperature Coefficient:X5R")
      (fields
        (field (name "Manufacturer Part") "CL21A106KAYNNNE")
        (field (name "Manufacturer") "SAMSUNG(三星)")
      )
      (libsource (lib "easyedapro") (part "CL21A106KAYNNNE"))
    )
    (comp (ref "C65")
      (value "10uF")
      (footprint "easyedapro:C0805")
      (description "Capacitance:10uF Tolerance:±10% Tolerance:±10% Voltage Rating:25V Temperature Coefficient:X5R")
      (fields
        (field (name "Manufacturer Part") "CL21A106KAYNNNE")
        (field (name "Manufacturer") "SAMSUNG(三星)")
      )
      (libsource (lib "easyedapro") (part "CL21A106KAYNNNE"))
    )
    (comp (ref "C80")
      (value "10uF")
      (footprint "easyedapro:C0805")
      (description "Capacitance:10uF Tolerance:±10% Tolerance:±10% Voltage Rating:25V Temperature Coefficient:X5R")
      (fields
        (field (name "Manufacturer Part") "CL21A106KAYNNNE")
        (field (name "Manufacturer") "SAMSUNG(三星)")
      )
      (libsource (lib "easyedapro") (part "CL21A106KAYNNNE"))
    )
    (comp (ref "C81")
      (value "10nF")
      (footprint "easyedapro:C0402")
      (description "Capacitance:10nF Tolerance:±10% Tolerance:±10% Voltage Rating:50V Temperature Coefficient:X7R")
      (fields
        (field (name "Manufacturer Part") "CL05B103KB5NNNC")
        (field (name "Manufacturer") "SAMSUNG(三星)")
      )
      (libsource (lib "easyedapro") (part "CL05B103KB5NNNC"))
    )
    (comp (ref "C82")
      (value "10uF")
      (footprint "easyedapro:C0805")
      (description "Capacitance:10uF Tolerance:±10% Tolerance:±10% Voltage Rating:25V Temperature Coefficient:X5R")
      (fields
        (field (name "Manufacturer Part") "CL21A106KAYNNNE")
        (field (name "Manufacturer") "SAMSUNG(三星)")
      )
      (libsource (lib "easyedapro") (part "CL21A106KAYNNNE"))
    )
    (comp (ref "C84")
      (value "470uF")
      (footprint "easyedapro:CAP-TH_BD10.0-P5.00-D1.0-FD")
      (fields (field (name "Manufacturer Part") "ERS1HM471G20OT") (field (name "Manufacturer") "AISHI(艾华集团)"))
      (libsource (lib "easyedapro") (part "ERS1HM471G20OT"))
    )
    (comp (ref "C85")
      (value "470uF")
      (footprint "easyedapro:CAP-TH_BD10.0-P5.00-D1.0-FD")
      (fields (field (name "Manufacturer Part") "ERS1HM471G20OT") (field (name "Manufacturer") "AISHI(艾华集团)"))
      (libsource (lib "easyedapro") (part "ERS1HM471G20OT"))
    )
    (comp (ref "C86")
      (value "470uF")
      (footprint "easyedapro:CAP-TH_BD10.0-P5.00-D1.0-FD")
      (fields (field (name "Manufacturer Part") "ERS1HM471G20OT") (field (name "Manufacturer") "AISHI(艾华集团)"))
      (libsource (lib "easyedapro") (part "ERS1HM471G20OT"))
    )
    (comp (ref "C103")
      (value "10uF")
      (footprint "easyedapro:C0805")
      (description "Capacitance:10uF Tolerance:±10% Tolerance:±10% Voltage Rating:25V Temperature Coefficient:X5R")
      (fields
        (field (name "Manufacturer Part") "CL21A106KAYNNNE")
        (field (name "Manufacturer") "SAMSUNG(三星)")
      )
      (libsource (lib "easyedapro") (part "CL21A106KAYNNNE"))
    )
    (comp (ref "C104")
      (value "10uF")
      (footprint "easyedapro:C0805")
      (description "Capacitance:10uF Tolerance:±10% Tolerance:±10% Voltage Rating:25V Temperature Coefficient:X5R")
      (fields
        (field (name "Manufacturer Part") "CL21A106KAYNNNE")
        (field (name "Manufacturer") "SAMSUNG(三星)")
      )
      (libsource (lib "easyedapro") (part "CL21A106KAYNNNE"))
    )
    (comp (ref "CN7")
      (value "DB142V-5.08-2P-GN")
      (footprint "easyedapro:CONN-TH_2P-P5.08_DIBO_DB142V-5.08-2P")
      (fields (field (name "Manufacturer") "DORABO(地博电气)"))
      (libsource (lib "easyedapro") (part "DB142V-5.08-2P"))
    )
    (comp (ref "CN34")
      (value "HX-XH2.54-2PZZ")
      (footprint "easyedapro:CONN-TH_2P-P2.50_HX-2.54MM-2P-ZZ-MS")
      (fields (field (name "Manufacturer") "hanxia(韩下)"))
      (libsource (lib "easyedapro") (part "HX-XH2.54-2PZZ"))
    )
    (comp (ref "CN35")
      (value "HX-XH2.54-2PZZ")
      (footprint "easyedapro:CONN-TH_2P-P2.50_HX-2.54MM-2P-ZZ-MS")
      (fields (field (name "Manufacturer") "hanxia(韩下)"))
      (libsource (lib "easyedapro") (part "HX-XH2.54-2PZZ"))
    )
    (comp (ref "D4")
      (value "SS34")
      (footprint "easyedapro:SMA_L4.3-W2.6-LS5.2-RD")
      (fields (field (name "Manufacturer") "MDD(辰达半导体)"))
      (libsource (lib "easyedapro") (part "SS34_C8678"))
    )
    (comp (ref "D5")
      (value "SS34")
      (footprint "easyedapro:SMA_L4.3-W2.6-LS5.2-RD")
      (fields (field (name "Manufacturer") "MDD(辰达半导体)"))
      (libsource (lib "easyedapro") (part "SS34_C8678"))
    )
    (comp (ref "D6")
      (value "SMBJ30CA-AT/TR13")
      (footprint "easyedapro:SMB_L4.3-W3.6-LS5.4-BI")
      (fields (field (name "Manufacturer") "Brightking(君耀电子)"))
      (libsource (lib "easyedapro") (part "SMBJ30CA-AT/TR13"))
    )
    (comp (ref "F1")
      (value "1812L150/33GR")
      (footprint "easyedapro:F1812")
      (fields (field (name "Manufacturer") "LUTE(陆特)"))
      (libsource (lib "easyedapro") (part "1812L150/33GR"))
    )
    (comp (ref "L6")
      (value "BLM21PG221SN1D")
      (footprint "easyedapro:L0805")
      (fields (field (name "Manufacturer") "muRata(村田)"))
      (libsource (lib "easyedapro") (part "BLM21PG221SN1D"))
    )
    (comp (ref "L7")
      (value "BLM21PG221SN1D")
      (footprint "easyedapro:L0805")
      (fields (field (name "Manufacturer") "muRata(村田)"))
      (libsource (lib "easyedapro") (part "BLM21PG221SN1D"))
    )
    (comp (ref "L14")
      (value "6.8uH")
      (footprint "easyedapro:IND-SMD_L7.0-W6.6")
      (fields (field (name "Manufacturer Part") "FXL0630-6R8-M") (field (name "Manufacturer") "cjiang(长江微电)"))
      (libsource (lib "easyedapro") (part "FXL0630-6R8-M"))
    )
    (comp (ref "R36")
      (value "10kΩ")
      (footprint "easyedapro:R0402")
      (fields
        (field (name "Manufacturer Part") "0402WGF1002TCE")
        (field (name "Manufacturer") "UNI-ROYAL(厚声)")
      )
      (libsource (lib "easyedapro") (part "0402WGF1002TCE"))
    )
    (comp (ref "R37")
      (value "56kΩ")
      (footprint "easyedapro:R0402")
      (fields
        (field (name "Manufacturer Part") "0402WGF5602TCE")
        (field (name "Manufacturer") "UNI-ROYAL(厚声)")
      )
      (libsource (lib "easyedapro") (part "0402WGF5602TCE"))
    )
    (comp (ref "U17")
      (value "EUP3458VIR1")
      (footprint "easyedapro:SOT-23-6_L2.9-W1.6-P0.95-LS2.8-BL")
      (fields (field (name "Manufacturer") "EUTECH(德信)"))
      (libsource (lib "easyedapro") (part "EUP3458VIR1"))
    )
    (comp (ref "C75")
      (value "100nF")
      (footprint "easyedapro:C0402")
      (description "Capacitance:100nF Tolerance:±10% Tolerance:±10% Voltage Rating:50V Temperature Coefficient:X7R")
      (fields
        (field (name "Manufacturer Part") "CL05B104KB54PNC")
        (field (name "Manufacturer") "SAMSUNG(三星)")
      )
      (libsource (lib "easyedapro") (part "CL05B104KB54PNC"))
    )
    (comp (ref "C77")
      (value "100nF")
      (footprint "easyedapro:C0402")
      (description "Capacitance:100nF Tolerance:±10% Tolerance:±10% Voltage Rating:50V Temperature Coefficient:X7R")
      (fields
        (field (name "Manufacturer Part") "CL05B104KB54PNC")
        (field (name "Manufacturer") "SAMSUNG(三星)")
      )
      (libsource (lib "easyedapro") (part "CL05B104KB54PNC"))
    )
    (comp (ref "CN6")
      (value "HX-XH2.54-3PZZ")
      (footprint "easyedapro:CONN-TH_3P-P2.50_HC-XH-3A-G")
      (fields (field (name "Manufacturer") "hanxia(韩下)"))
      (libsource (lib "easyedapro") (part "HX-XH2.54-3PZZ"))
    )
    (comp (ref "D1")
      (value "1N4148WS")
      (footprint "easyedapro:SOD-323_L1.8-W1.3-LS2.5-RD")
      (fields (field (name "Manufacturer") "CJ(江苏长电/长晶)"))
      (libsource (lib "easyedapro") (part "1N4148WS T4"))
    )
    (comp (ref "D2")
      (value "RCLAMP0521P-N")
      (footprint "easyedapro:X1-DFN1006-2_L1.0-W0.6-P0.65-BI")
      (fields (field (name "Manufacturer") "BORN(伯恩半导体)"))
      (libsource (lib "easyedapro") (part "RCLAMP0521P-N"))
    )
    (comp (ref "D3")
      (value "RCLAMP0521P-N")
      (footprint "easyedapro:X1-DFN1006-2_L1.0-W0.6-P0.65-BI")
      (fields (field (name "Manufacturer") "BORN(伯恩半导体)"))
      (libsource (lib "easyedapro") (part "RCLAMP0521P-N"))
    )
    (comp (ref "L12")
      (value "BLM18PG121SN1D")
      (footprint "easyedapro:L0603")
      (fields (field (name "Manufacturer") "muRata(村田)"))
      (libsource (lib "easyedapro") (part "BLM18PG121SN1D_C14709"))
    )
    (comp (ref "L13")
      (value "BLM18PG121SN1D")
      (footprint "easyedapro:L0603")
      (fields (field (name "Manufacturer") "muRata(村田)"))
      (libsource (lib "easyedapro") (part "BLM18PG121SN1D_C14709"))
    )
    (comp (ref "R29")
      (value "4.7kΩ")
      (footprint "easyedapro:R0603")
      (fields
        (field (name "Manufacturer Part") "0603WAF4701T5E")
        (field (name "Manufacturer") "UNI-ROYAL(厚声)")
      )
      (libsource (lib "easyedapro") (part "0603WAF4701T5E"))
    )
    (comp (ref "R31")
      (value "220Ω")
      (footprint "easyedapro:R0603")
      (fields
        (field (name "Manufacturer Part") "0603WAF2200T5E")
        (field (name "Manufacturer") "UNI-ROYAL(厚声)")
      )
      (libsource (lib "easyedapro") (part "0603WAF2200T5E"))
    )
    (comp (ref "R32")
      (value "1MΩ")
      (footprint "easyedapro:R0603")
      (fields
        (field (name "Manufacturer Part") "0603WAF1004T5E")
        (field (name "Manufacturer") "UNI-ROYAL(厚声)")
      )
      (libsource (lib "easyedapro") (part "0603WAF1004T5E"))
    )
    (comp (ref "U15")
      (value "6N137S1(TA)")
      (footprint "easyedapro:SMD-8_L9.8-W6.6-P2.54-LS10.3-BL")
      (fields (field (name "Manufacturer") "EVERLIGHT(亿光)"))
      (libsource (lib "easyedapro") (part "6N137S1(TA)"))
    )
    (comp (ref "C37")
      (value "100nF")
      (footprint "easyedapro:C0603")
      (fields
        (field (name "Manufacturer Part") "CC0603KRX7R9BB104")
        (field (name "Manufacturer") "YAGEO(国巨)")
      )
      (libsource (lib "easyedapro") (part "CC0603KRX7R9BB104"))
    )
    (comp (ref "C87")
      (value "1uF")
      (footprint "easyedapro:C0402")
      (description "Capacitance:1uF Tolerance:±10% Tolerance:±10% Voltage Rating:25V Temperature Coefficient:X5R")
      (fields
        (field (name "Manufacturer Part") "CL05A105KA5NQNC")
        (field (name "Manufacturer") "SAMSUNG(三星)")
      )
      (libsource (lib "easyedapro") (part "CL05A105KA5NQNC"))
    )
    (comp (ref "C88")
      (value "1uF")
      (footprint "easyedapro:C0402")
      (description "Capacitance:1uF Tolerance:±10% Tolerance:±10% Voltage Rating:25V Temperature Coefficient:X5R")
      (fields
        (field (name "Manufacturer Part") "CL05A105KA5NQNC")
        (field (name "Manufacturer") "SAMSUNG(三星)")
      )
      (libsource (lib "easyedapro") (part "CL05A105KA5NQNC"))
    )
    (comp (ref "C89")
      (value "22uF")
      (footprint "easyedapro:C0805")
      (description "Capacitance:22uF Tolerance:±20% Tolerance:±20% Voltage Rating:25V Temperature Coefficient:X5R")
      (fields
        (field (name "Manufacturer Part") "CL21A226MAQNNNE")
        (field (name "Manufacturer") "SAMSUNG(三星)")
      )
      (libsource (lib "easyedapro") (part "CL21A226MAQNNNE"))
    )
    (comp (ref "C90")
      (value "10uF")
      (footprint "easyedapro:C0805")
      (description "Capacitance:10uF Tolerance:±10% Tolerance:±10% Voltage Rating:25V Temperature Coefficient:X5R")
      (fields
        (field (name "Manufacturer Part") "CL21A106KAYNNNE")
        (field (name "Manufacturer") "SAMSUNG(三星)")
      )
      (libsource (lib "easyedapro") (part "CL21A106KAYNNNE"))
    )
    (comp (ref "C91")
      (value "10uF")
      (footprint "easyedapro:C0805")
      (description "Capacitance:10uF Tolerance:±10% Tolerance:±10% Voltage Rating:25V Temperature Coefficient:X5R")
      (fields
        (field (name "Manufacturer Part") "CL21A106KAYNNNE")
        (field (name "Manufacturer") "SAMSUNG(三星)")
      )
      (libsource (lib "easyedapro") (part "CL21A106KAYNNNE"))
    )
    (comp (ref "C92")
      (value "10uF")
      (footprint "easyedapro:C0805")
      (description "Capacitance:10uF Tolerance:±10% Tolerance:±10% Voltage Rating:25V Temperature Coefficient:X5R")
      (fields
        (field (name "Manufacturer Part") "CL21A106KAYNNNE")
        (field (name "Manufacturer") "SAMSUNG(三星)")
      )
      (libsource (lib "easyedapro") (part "CL21A106KAYNNNE"))
    )
    (comp (ref "C102")
      (value "1uF")
      (footprint "easyedapro:C0402")
      (description "Capacitance:1uF Tolerance:±10% Tolerance:±10% Voltage Rating:25V Temperature Coefficient:X5R")
      (fields
        (field (name "Manufacturer Part") "CL05A105KA5NQNC")
        (field (name "Manufacturer") "SAMSUNG(三星)")
      )
      (libsource (lib "easyedapro") (part "CL05A105KA5NQNC"))
    )
    (comp (ref "C105")
      (value "1uF")
      (footprint "easyedapro:C0402")
      (description "Capacitance:1uF Tolerance:±10% Tolerance:±10% Voltage Rating:25V Temperature Coefficient:X5R")
      (fields
        (field (name "Manufacturer Part") "CL05A105KA5NQNC")
        (field (name "Manufacturer") "SAMSUNG(三星)")
      )
      (libsource (lib "easyedapro") (part "CL05A105KA5NQNC"))
    )
    (comp (ref "CARD1")
      (value "TF-01A")
      (footprint "easyedapro:TF-SMD_TF-01A")
      (fields (field (name "Manufacturer") "韩国韩荣"))
      (libsource (lib "easyedapro") (part "TF-01A"))
    )
    (comp (ref "CN8")
      (value "HX-XH2.54-2PZZ")
      (footprint "easyedapro:CONN-TH_2P-P2.50_HX-2.54MM-2P-ZZ-MS")
      (fields (field (name "Manufacturer") "hanxia(韩下)"))
      (libsource (lib "easyedapro") (part "HX-XH2.54-2PZZ"))
    )
    (comp (ref "CN9")
      (value "HX-XH2.54-2PZZ")
      (footprint "easyedapro:CONN-TH_2P-P2.50_HX-2.54MM-2P-ZZ-MS")
      (fields (field (name "Manufacturer") "hanxia(韩下)"))
      (libsource (lib "easyedapro") (part "HX-XH2.54-2PZZ"))
    )
    (comp (ref "CN10")
      (value "HX-XH2.54-2PZZ")
      (footprint "easyedapro:CONN-TH_2P-P2.50_HX-2.54MM-2P-ZZ-MS")
      (fields (field (name "Manufacturer") "hanxia(韩下)"))
      (libsource (lib "easyedapro") (part "HX-XH2.54-2PZZ"))
    )
    (comp (ref "CN11")
      (value "HX-XH2.54-2PZZ")
      (footprint "easyedapro:CONN-TH_2P-P2.50_HX-2.54MM-2P-ZZ-MS")
      (fields (field (name "Manufacturer") "hanxia(韩下)"))
      (libsource (lib "easyedapro") (part "HX-XH2.54-2PZZ"))
    )
    (comp (ref "CN12")
      (value "HX-XH2.54-2PZZ")
      (footprint "easyedapro:CONN-TH_2P-P2.50_HX-2.54MM-2P-ZZ-MS")
      (fields (field (name "Manufacturer") "hanxia(韩下)"))
      (libsource (lib "easyedapro") (part "HX-XH2.54-2PZZ"))
    )
    (comp (ref "CN13")
      (value "HX-XH2.54-2PZZ")
      (footprint "easyedapro:CONN-TH_2P-P2.50_HX-2.54MM-2P-ZZ-MS")
      (fields (field (name "Manufacturer") "hanxia(韩下)"))
      (libsource (lib "easyedapro") (part "HX-XH2.54-2PZZ"))
    )
    (comp (ref "CN14")
      (value "HX-XH2.54-2PZZ")
      (footprint "easyedapro:CONN-TH_2P-P2.50_HX-2.54MM-2P-ZZ-MS")
      (fields (field (name "Manufacturer") "hanxia(韩下)"))
      (libsource (lib "easyedapro") (part "HX-XH2.54-2PZZ"))
    )
    (comp (ref "CN15")
      (value "HX-XH2.54-2PZZ")
      (footprint "easyedapro:CONN-TH_2P-P2.50_HX-2.54MM-2P-ZZ-MS")
      (fields (field (name "Manufacturer") "hanxia(韩下)"))
      (libsource (lib "easyedapro") (part "HX-XH2.54-2PZZ"))
    )
    (comp (ref "CN16")
      (value "HX-XH2.54-2PZZ")
      (footprint "easyedapro:CONN-TH_2P-P2.50_HX-2.54MM-2P-ZZ-MS")
      (fields (field (name "Manufacturer") "hanxia(韩下)"))
      (libsource (lib "easyedapro") (part "HX-XH2.54-2PZZ"))
    )
    (comp (ref "CN17")
      (value "HX-XH2.54-2PZZ")
      (footprint "easyedapro:CONN-TH_2P-P2.50_HX-2.54MM-2P-ZZ-MS")
      (fields (field (name "Manufacturer") "hanxia(韩下)"))
      (libsource (lib "easyedapro") (part "HX-XH2.54-2PZZ"))
    )
    (comp (ref "CN20")
      (value "HX-XH2.54-2PZZ")
      (footprint "easyedapro:CONN-TH_2P-P2.50_HX-2.54MM-2P-ZZ-MS")
      (fields (field (name "Manufacturer") "hanxia(韩下)"))
      (libsource (lib "easyedapro") (part "HX-XH2.54-2PZZ"))
    )
    (comp (ref "CN21")
      (value "HX-XH2.54-2PZZ")
      (footprint "easyedapro:CONN-TH_2P-P2.50_HX-2.54MM-2P-ZZ-MS")
      (fields (field (name "Manufacturer") "hanxia(韩下)"))
      (libsource (lib "easyedapro") (part "HX-XH2.54-2PZZ"))
    )
    (comp (ref "CN22")
      (value "HX-XH2.54-3PZZ")
      (footprint "easyedapro:CONN-TH_3P-P2.50_HC-XH-3A-G")
      (fields (field (name "Manufacturer") "hanxia(韩下)"))
      (libsource (lib "easyedapro") (part "HX-XH2.54-3PZZ"))
    )
    (comp (ref "CN24")
      (value "HX-XH2.54-2PZZ")
      (footprint "easyedapro:CONN-TH_2P-P2.50_HX-2.54MM-2P-ZZ-MS")
      (fields (field (name "Manufacturer") "hanxia(韩下)"))
      (libsource (lib "easyedapro") (part "HX-XH2.54-2PZZ"))
    )
    (comp (ref "CN25")
      (value "HX-XH2.54-3PZZ")
      (footprint "easyedapro:CONN-TH_3P-P2.50_HC-XH-3A-G")
      (fields (field (name "Manufacturer") "hanxia(韩下)"))
      (libsource (lib "easyedapro") (part "HX-XH2.54-3PZZ"))
    )
    (comp (ref "CN26")
      (value "HX-XH2.54-3PZZ")
      (footprint "easyedapro:CONN-TH_3P-P2.50_HC-XH-3A-G")
      (fields (field (name "Manufacturer") "hanxia(韩下)"))
      (libsource (lib "easyedapro") (part "HX-XH2.54-3PZZ"))
    )
    (comp (ref "CN29")
      (value "HX-XH2.54-2PZZ")
      (footprint "easyedapro:CONN-TH_2P-P2.50_HX-2.54MM-2P-ZZ-MS")
      (fields (field (name "Manufacturer") "hanxia(韩下)"))
      (libsource (lib "easyedapro") (part "HX-XH2.54-2PZZ"))
    )
    (comp (ref "CN30")
      (value "HX-XH2.54-4PZZ")
      (footprint "easyedapro:CONN-TH_4P-P2.50-XH2.54-4P")
      (fields (field (name "Manufacturer") "hanxia(韩下)"))
      (libsource (lib "easyedapro") (part "HX-XH2.54-4PZZ"))
    )
    (comp (ref "CN31")
      (value "HX-XH2.54-4PZZ")
      (footprint "easyedapro:CONN-TH_4P-P2.50-XH2.54-4P")
      (fields (field (name "Manufacturer") "hanxia(韩下)"))
      (libsource (lib "easyedapro") (part "HX-XH2.54-4PZZ"))
    )
    (comp (ref "CN32")
      (value "HX-XH2.54-4PZZ")
      (footprint "easyedapro:CONN-TH_4P-P2.50-XH2.54-4P")
      (fields (field (name "Manufacturer") "hanxia(韩下)"))
      (libsource (lib "easyedapro") (part "HX-XH2.54-4PZZ"))
    )
    (comp (ref "CN36")
      (value "HX-XH2.54-4PZZ")
      (footprint "easyedapro:CONN-TH_4P-P2.50-XH2.54-4P")
      (fields (field (name "Manufacturer") "hanxia(韩下)"))
      (libsource (lib "easyedapro") (part "HX-XH2.54-4PZZ"))
    )
    (comp (ref "D7")
      (value "SS34")
      (footprint "easyedapro:SMA_L4.3-W2.6-LS5.2-RD")
      (fields (field (name "Manufacturer") "MDD(辰达半导体)"))
      (libsource (lib "easyedapro") (part "SS34_C8678"))
    )
    (comp (ref "R38")
      (value "10kΩ")
      (footprint "easyedapro:R0402")
      (fields
        (field (name "Manufacturer Part") "0402WGF1002TCE")
        (field (name "Manufacturer") "UNI-ROYAL(厚声)")
      )
      (libsource (lib "easyedapro") (part "0402WGF1002TCE"))
    )
    (comp (ref "R39")
      (value "680Ω")
      (footprint "easyedapro:R0402")
      (fields
        (field (name "Manufacturer Part") "0402WGF6800TCE")
        (field (name "Manufacturer") "UNI-ROYAL(厚声)")
      )
      (libsource (lib "easyedapro") (part "0402WGF6800TCE"))
    )
    (comp (ref "R40")
      (value "1.5kΩ")
      (footprint "easyedapro:R0402")
      (fields
        (field (name "Manufacturer Part") "0402WGF1501TCE")
        (field (name "Manufacturer") "UNI-ROYAL(厚声)")
      )
      (libsource (lib "easyedapro") (part "0402WGF1501TCE"))
    )
    (comp (ref "R41")
      (value "3.9kΩ")
      (footprint "easyedapro:R0402")
      (fields
        (field (name "Manufacturer Part") "0402WGJ0392TCE")
        (field (name "Manufacturer") "UNI-ROYAL(厚声)")
      )
      (libsource (lib "easyedapro") (part "0402WGJ0392TCE_C11925"))
    )
    (comp (ref "R42")
      (value "5.6kΩ")
      (footprint "easyedapro:R0402")
      (fields
        (field (name "Manufacturer Part") "0402WGF5601TCE")
        (field (name "Manufacturer") "UNI-ROYAL(厚声)")
      )
      (libsource (lib "easyedapro") (part "0402WGF5601TCE"))
    )
    (comp (ref "R43")
      (value "8.2kΩ")
      (footprint "easyedapro:R0402")
      (fields
        (field (name "Manufacturer Part") "0402WGF8201TCE")
        (field (name "Manufacturer") "UNI-ROYAL(厚声)")
      )
      (libsource (lib "easyedapro") (part "0402WGF8201TCE"))
    )
    (comp (ref "R44")
      (value "12kΩ")
      (footprint "easyedapro:R0402")
      (fields
        (field (name "Manufacturer Part") "0402WGJ0123TCE")
        (field (name "Manufacturer") "UNI-ROYAL(厚声)")
      )
      (libsource (lib "easyedapro") (part "0402WGJ0123TCE"))
    )
    (comp (ref "R45")
      (value "18kΩ")
      (footprint "easyedapro:R0402")
      (fields
        (field (name "Manufacturer Part") "0402WGJ0183TCE")
        (field (name "Manufacturer") "UNI-ROYAL(厚声)")
      )
      (libsource (lib "easyedapro") (part "0402WGJ0183TCE"))
    )
    (comp (ref "R46")
      (value "33kΩ")
      (footprint "easyedapro:R0402")
      (fields
        (field (name "Manufacturer Part") "0402WGF3302TCE")
        (field (name "Manufacturer") "UNI-ROYAL(厚声)")
      )
      (libsource (lib "easyedapro") (part "0402WGF3302TCE"))
    )
    (comp (ref "R47")
      (value "2.4kΩ")
      (footprint "easyedapro:R0402")
      (fields
        (field (name "Manufacturer Part") "0402WGF2401TCE")
        (field (name "Manufacturer") "UNI-ROYAL(厚声)")
      )
      (libsource (lib "easyedapro") (part "0402WGF2401TCE"))
    )
    (comp (ref "R48")
      (value "10kΩ")
      (footprint "easyedapro:R0402")
      (fields
        (field (name "Manufacturer Part") "0402WGF1002TCE")
        (field (name "Manufacturer") "UNI-ROYAL(厚声)")
      )
      (libsource (lib "easyedapro") (part "0402WGF1002TCE"))
    )
    (comp (ref "R49")
      (value "10kΩ")
      (footprint "easyedapro:R0402")
      (fields
        (field (name "Manufacturer Part") "0402WGF1002TCE")
        (field (name "Manufacturer") "UNI-ROYAL(厚声)")
      )
      (libsource (lib "easyedapro") (part "0402WGF1002TCE"))
    )
    (comp (ref "R52")
      (value "1.5kΩ")
      (footprint "easyedapro:R0402")
      (fields
        (field (name "Manufacturer Part") "0402WGF1501TCE")
        (field (name "Manufacturer") "UNI-ROYAL(厚声)")
      )
      (libsource (lib "easyedapro") (part "0402WGF1501TCE"))
    )
    (comp (ref "R53")
      (value "1.5kΩ")
      (footprint "easyedapro:R0402")
      (fields
        (field (name "Manufacturer Part") "0402WGF1501TCE")
        (field (name "Manufacturer") "UNI-ROYAL(厚声)")
      )
      (libsource (lib "easyedapro") (part "0402WGF1501TCE"))
    )
    (comp (ref "R54")
      (value "10kΩ")
      (footprint "easyedapro:R0402")
      (fields
        (field (name "Manufacturer Part") "0402WGF1002TCE")
        (field (name "Manufacturer") "UNI-ROYAL(厚声)")
      )
      (libsource (lib "easyedapro") (part "0402WGF1002TCE"))
    )
    (comp (ref "R55")
      (value "10kΩ")
      (footprint "easyedapro:R0402")
      (fields
        (field (name "Manufacturer Part") "0402WGF1002TCE")
        (field (name "Manufacturer") "UNI-ROYAL(厚声)")
      )
      (libsource (lib "easyedapro") (part "0402WGF1002TCE"))
    )
    (comp (ref "R56")
      (value "10kΩ")
      (footprint "easyedapro:R0402")
      (fields
        (field (name "Manufacturer Part") "0402WGF1002TCE")
        (field (name "Manufacturer") "UNI-ROYAL(厚声)")
      )
      (libsource (lib "easyedapro") (part "0402WGF1002TCE"))
    )
    (comp (ref "R57")
      (value "10kΩ")
      (footprint "easyedapro:R0402")
      (fields
        (field (name "Manufacturer Part") "0402WGF1002TCE")
        (field (name "Manufacturer") "UNI-ROYAL(厚声)")
      )
      (libsource (lib "easyedapro") (part "0402WGF1002TCE"))
    )
    (comp (ref "R58")
      (value "10kΩ")
      (footprint "easyedapro:R0402")
      (fields
        (field (name "Manufacturer Part") "0402WGF1002TCE")
        (field (name "Manufacturer") "UNI-ROYAL(厚声)")
      )
      (libsource (lib "easyedapro") (part "0402WGF1002TCE"))
    )
    (comp (ref "R59")
      (value "10kΩ")
      (footprint "easyedapro:R0402")
      (fields
        (field (name "Manufacturer Part") "0402WGF1002TCE")
        (field (name "Manufacturer") "UNI-ROYAL(厚声)")
      )
      (libsource (lib "easyedapro") (part "0402WGF1002TCE"))
    )
    (comp (ref "R60")
      (value "22Ω")
      (footprint "easyedapro:R0402")
      (fields
        (field (name "Manufacturer Part") "0402WGF220JTCE")
        (field (name "Manufacturer") "UNI-ROYAL(厚声)")
      )
      (libsource (lib "easyedapro") (part "0402WGF220JTCE"))
    )
    (comp (ref "R61")
      (value "22Ω")
      (footprint "easyedapro:R0402")
      (fields
        (field (name "Manufacturer Part") "0402WGF220JTCE")
        (field (name "Manufacturer") "UNI-ROYAL(厚声)")
      )
      (libsource (lib "easyedapro") (part "0402WGF220JTCE"))
    )
    (comp (ref "R62")
      (value "22Ω")
      (footprint "easyedapro:R0402")
      (fields
        (field (name "Manufacturer Part") "0402WGF220JTCE")
        (field (name "Manufacturer") "UNI-ROYAL(厚声)")
      )
      (libsource (lib "easyedapro") (part "0402WGF220JTCE"))
    )
    (comp (ref "R63")
      (value "22Ω")
      (footprint "easyedapro:R0402")
      (fields
        (field (name "Manufacturer Part") "0402WGF220JTCE")
        (field (name "Manufacturer") "UNI-ROYAL(厚声)")
      )
      (libsource (lib "easyedapro") (part "0402WGF220JTCE"))
    )
    (comp (ref "R64")
      (value "30kΩ")
      (footprint "easyedapro:R0603")
      (fields
        (field (name "Manufacturer Part") "0603WAF3002T5E")
        (field (name "Manufacturer") "UNI-ROYAL(厚声)")
      )
      (libsource (lib "easyedapro") (part "0603WAF3002T5E"))
    )
    (comp (ref "R65")
      (value "0Ω")
      (footprint "easyedapro:R0805")
      (fields
        (field (name "Manufacturer Part") "0805W8F0000T5E")
        (field (name "Manufacturer") "UNI-ROYAL(厚声)")
      )
      (libsource (lib "easyedapro") (part "0805W8F0000T5E"))
    )
    (comp (ref "R66")
      (value "0Ω")
      (footprint "easyedapro:R0805")
      (fields
        (field (name "Manufacturer Part") "0805W8F0000T5E")
        (field (name "Manufacturer") "UNI-ROYAL(厚声)")
      )
      (libsource (lib "easyedapro") (part "0805W8F0000T5E"))
    )
    (comp (ref "R67")
      (value "10kΩ")
      (footprint "easyedapro:R0402")
      (fields
        (field (name "Manufacturer Part") "0402WGF1002TCE")
        (field (name "Manufacturer") "UNI-ROYAL(厚声)")
      )
      (libsource (lib "easyedapro") (part "0402WGF1002TCE"))
    )
    (comp (ref "R68")
      (value "10kΩ")
      (footprint "easyedapro:R0402")
      (fields
        (field (name "Manufacturer Part") "0402WGF1002TCE")
        (field (name "Manufacturer") "UNI-ROYAL(厚声)")
      )
      (libsource (lib "easyedapro") (part "0402WGF1002TCE"))
    )
    (comp (ref "R69")
      (value "22Ω")
      (footprint "easyedapro:R0402")
      (fields
        (field (name "Manufacturer Part") "0402WGF220JTCE")
        (field (name "Manufacturer") "UNI-ROYAL(厚声)")
      )
      (libsource (lib "easyedapro") (part "0402WGF220JTCE"))
    )
    (comp (ref "R70")
      (value "22Ω")
      (footprint "easyedapro:R0402")
      (fields
        (field (name "Manufacturer Part") "0402WGF220JTCE")
        (field (name "Manufacturer") "UNI-ROYAL(厚声)")
      )
      (libsource (lib "easyedapro") (part "0402WGF220JTCE"))
    )
    (comp (ref "R71")
      (value "22Ω")
      (footprint "easyedapro:R0402")
      (fields
        (field (name "Manufacturer Part") "0402WGF220JTCE")
        (field (name "Manufacturer") "UNI-ROYAL(厚声)")
      )
      (libsource (lib "easyedapro") (part "0402WGF220JTCE"))
    )
    (comp (ref "R72")
      (value "22Ω")
      (footprint "easyedapro:R0402")
      (fields
        (field (name "Manufacturer Part") "0402WGF220JTCE")
        (field (name "Manufacturer") "UNI-ROYAL(厚声)")
      )
      (libsource (lib "easyedapro") (part "0402WGF220JTCE"))
    )
    (comp (ref "R73")
      (value "10kΩ")
      (footprint "easyedapro:R0402")
      (fields
        (field (name "Manufacturer Part") "0402WGF1002TCE")
        (field (name "Manufacturer") "UNI-ROYAL(厚声)")
      )
      (libsource (lib "easyedapro") (part "0402WGF1002TCE"))
    )
    (comp (ref "U12")
      (value "DRV8871DDAR")
      (footprint "easyedapro:SO-8_L4.9-W3.9-P1.27-LS6.0-BL-EP")
      (fields (field (name "Manufacturer") "TI(德州仪器)"))
      (libsource (lib "easyedapro") (part "DRV8871DDAR"))
    )
    (comp (ref "U16")
      (value "ESP32-S3-NANO")
      (footprint "easyedapro:COMM-TH_43.2-W17.8-P2.54_ESP32-S3")
      (fields (field (name "Manufacturer") "Waveshare(微雪电子)"))
      (libsource (lib "easyedapro") (part "ESP32-S3_C22438991"))
    )
  )
  (nets
    (net (code "1") (name "2V5A") (class "Default")
      (node (ref "C43") (pin "2") (pinfunction "2_2") (pintype "input"))
      (node (ref "C44") (pin "2") (pinfunction "2_2") (pintype "input"))
      (node (ref "C46") (pin "1") (pinfunction "1_1") (pintype "input"))
      (node (ref "C50") (pin "1") (pinfunction "1_1") (pintype "input"))
      (node (ref "R13") (pin "2") (pinfunction "2_2") (pintype "input"))
      (node (ref "R14") (pin "1") (pinfunction "1_1") (pintype "input"))
      (node (ref "R21") (pin "2") (pinfunction "2_2") (pintype "input"))
      (node (ref "R7") (pin "2") (pinfunction "2_2") (pintype "input"))
      (node (ref "R9") (pin "1") (pinfunction "1_1") (pintype "input"))
      (node (ref "U2") (pin "2") (pinfunction "VOCM_2") (pintype "unspecified"))
      (node (ref "U6") (pin "2") (pinfunction "VOCM_2") (pintype "unspecified"))
    )
    (net (code "2") (name "3V3") (class "Default")
      (node (ref "C102") (pin "2") (pinfunction "2_2") (pintype "unspecified"))
      (node (ref "C105") (pin "2") (pinfunction "2_2") (pintype "unspecified"))
      (node (ref "C22") (pin "1") (pinfunction "1_1") (pintype "input"))
      (node (ref "C28") (pin "1") (pinfunction "1_1") (pintype "input"))
      (node (ref "C29") (pin "1") (pinfunction "1_1") (pintype "unspecified"))
      (node (ref "C30") (pin "1") (pinfunction "1_1") (pintype "unspecified"))
      (node (ref "C32") (pin "1") (pinfunction "1_1") (pintype "unspecified"))
      (node (ref "C8") (pin "1") (pinfunction "1_1") (pintype "unspecified"))
      (node (ref "C87") (pin "1") (pinfunction "1_1") (pintype "unspecified"))
      (node (ref "CARD1") (pin "4") (pinfunction "VDD_4") (pintype "input"))
      (node (ref "CN20") (pin "2") (pinfunction "2_2") (pintype "unspecified"))
      (node (ref "CN21") (pin "2") (pinfunction "2_2") (pintype "unspecified"))
      (node (ref "CN32") (pin "2") (pinfunction "2_2") (pintype "unspecified"))
      (node (ref "CN36") (pin "2") (pinfunction "2_2") (pintype "unspecified"))
      (node (ref "L1") (pin "1") (pinfunction "1_1") (pintype "unspecified"))
      (node (ref "R29") (pin "2") (pinfunction "2_2") (pintype "input"))
      (node (ref "R38") (pin "2") (pinfunction "2_2") (pintype "input"))
      (node (ref "R48") (pin "1") (pinfunction "1_1") (pintype "input"))
      (node (ref "R49") (pin "1") (pinfunction "1_1") (pintype "input"))
      (node (ref "R54") (pin "1") (pinfunction "1_1") (pintype "input"))
      (node (ref "R55") (pin "1") (pinfunction "1_1") (pintype "input"))
      (node (ref "R56") (pin "1") (pinfunction "1_1") (pintype "input"))
      (node (ref "R57") (pin "1") (pinfunction "1_1") (pintype "input"))
      (node (ref "R58") (pin "1") (pinfunction "1_1") (pintype "input"))
      (node (ref "R59") (pin "1") (pinfunction "1_1") (pintype "input"))
      (node (ref "R73") (pin "1") (pinfunction "1_1") (pintype "input"))
      (node (ref "U1") (pin "17") (pinfunction "XSMT_17") (pintype "input"))
      (node (ref "U1") (pin "20") (pinfunction "DVDD_20") (pintype "input"))
      (node (ref "U14") (pin "5") (pinfunction "OUT_5") (pintype "unspecified"))
    )
    (net (code "3") (name "3V3A") (class "Default")
      (node (ref "C12") (pin "2") (pinfunction "2_2") (pintype "unspecified"))
      (node (ref "C14") (pin "1") (pinfunction "1_1") (pintype "unspecified"))
      (node (ref "C24") (pin "1") (pinfunction "1_1") (pintype "input"))
      (node (ref "C25") (pin "2") (pinfunction "2_2") (pintype "input"))
      (node (ref "C73") (pin "1") (pinfunction "1_1") (pintype "unspecified"))
      (node (ref "L11") (pin "2") (pinfunction "2_2") (pintype "unspecified"))
      (node (ref "U1") (pin "1") (pinfunction "CPVDD_1") (pintype "input"))
      (node (ref "U1") (pin "8") (pinfunction "AVDD_8") (pintype "input"))
    )
    (net (code "4") (name "3V3ESP") (class "Default")
      (node (ref "C92") (pin "2") (pinfunction "2_2") (pintype "unspecified"))
      (node (ref "R68") (pin "2") (pinfunction "2_2") (pintype "input"))
      (node (ref "U16") (pin "17") (pinfunction "3V3_17") (pintype "unspecified"))
    )
    (net (code "5") (name "5V") (class "Default")
      (node (ref "C103") (pin "1") (pinfunction "1_1") (pintype "unspecified"))
      (node (ref "C104") (pin "1") (pinfunction "1_1") (pintype "unspecified"))
      (node (ref "C26") (pin "1") (pinfunction "1_1") (pintype "unspecified"))
      (node (ref "C27") (pin "1") (pinfunction "1_1") (pintype "input"))
      (node (ref "C65") (pin "1") (pinfunction "1_1") (pintype "unspecified"))
      (node (ref "C71") (pin "2") (pinfunction "2_2") (pintype "unspecified"))
      (node (ref "C75") (pin "1") (pinfunction "1_1") (pintype "input"))
      (node (ref "C86") (pin "1") (pinfunction "1_1") (pintype "input"))
      (node (ref "C90") (pin "1") (pinfunction "1_1") (pintype "unspecified"))
      (node (ref "CN30") (pin "2") (pinfunction "2_2") (pintype "unspecified"))
      (node (ref "CN31") (pin "2") (pinfunction "2_2") (pintype "unspecified"))
      (node (ref "CN34") (pin "2") (pinfunction "2_2") (pintype "unspecified"))
      (node (ref "CN35") (pin "2") (pinfunction "2_2") (pintype "unspecified"))
      (node (ref "D7") (pin "2") (pinfunction "A_2") (pintype "unspecified"))
      (node (ref "L2") (pin "1") (pinfunction "1_1") (pintype "unspecified"))
      (node (ref "L7") (pin "1") (pinfunction "1_1") (pintype "unspecified"))
      (node (ref "U14") (pin "1") (pinfunction "IN_1") (pintype "unspecified"))
      (node (ref "U14") (pin "3") (pinfunction "EN_3") (pintype "unspecified"))
      (node (ref "U15") (pin "7") (pinfunction "VE_7") (pintype "unspecified"))
      (node (ref "U15") (pin "8") (pinfunction "VCC_8") (pintype "unspecified"))
    )
    (net (code "6") (name "5VA") (class "Default")
      (node (ref "C39") (pin "1") (pinfunction "1_1") (pintype "unspecified"))
      (node (ref "C40") (pin "1") (pinfunction "1_1") (pintype "unspecified"))
      (node (ref "C41") (pin "1") (pinfunction "1_1") (pintype "input"))
      (node (ref "C42") (pin "2") (pinfunction "2_2") (pintype "unspecified"))
      (node (ref "C47") (pin "1") (pinfunction "1_1") (pintype "unspecified"))
      (node (ref "C48") (pin "2") (pinfunction "2_2") (pintype "input"))
      (node (ref "C51") (pin "1") (pinfunction "1_1") (pintype "unspecified"))
      (node (ref "C52") (pin "2") (pinfunction "2_2") (pintype "input"))
      (node (ref "C68") (pin "1") (pinfunction "1_1") (pintype "unspecified"))
      (node (ref "L9") (pin "1") (pinfunction "1_1") (pintype "unspecified"))
      (node (ref "R12") (pin "2") (pinfunction "2_2") (pintype "input"))
      (node (ref "R3") (pin "2") (pinfunction "2_2") (pintype "input"))
      (node (ref "R5") (pin "2") (pinfunction "2_2") (pintype "input"))
      (node (ref "U2") (pin "3") (pinfunction "V+_3") (pintype "unspecified"))
      (node (ref "U3") (pin "5") (pinfunction "V+_5") (pintype "unspecified"))
      (node (ref "U6") (pin "3") (pinfunction "V+_3") (pintype "unspecified"))
    )
    (net (code "7") (name "5V_P") (class "Default")
      (node (ref "C59") (pin "1") (pinfunction "1_1") (pintype "unspecified"))
      (node (ref "C82") (pin "1") (pinfunction "1_1") (pintype "unspecified"))
      (node (ref "C84") (pin "1") (pinfunction "1_1") (pintype "input"))
      (node (ref "C91") (pin "1") (pinfunction "1_1") (pintype "unspecified"))
      (node (ref "CN25") (pin "2") (pinfunction "2_2") (pintype "unspecified"))
      (node (ref "CN26") (pin "2") (pinfunction "2_2") (pintype "unspecified"))
      (node (ref "L14") (pin "2") (pinfunction "2_2") (pintype "unspecified"))
      (node (ref "L6") (pin "2") (pinfunction "2_2") (pintype "unspecified"))
      (node (ref "R37") (pin "2") (pinfunction "2_2") (pintype "input"))
      (node (ref "R66") (pin "2") (pinfunction "2_2") (pintype "input"))
    )
    (net (code "8") (name "BCK") (class "Default")
      (node (ref "CN33") (pin "2") (pinfunction "2_2") (pintype "unspecified"))
      (node (ref "R62") (pin "1") (pinfunction "1_1") (pintype "input"))
      (node (ref "U1") (pin "13") (pinfunction "BCK_13") (pintype "input"))
    )
    (net (code "9") (name "BIN") (class "Default")
      (node (ref "CN33") (pin "3") (pinfunction "3_3") (pintype "unspecified"))
      (node (ref "R63") (pin "1") (pinfunction "1_1") (pintype "input"))
      (node (ref "U1") (pin "14") (pinfunction "DIN_14") (pintype "input"))
    )
    (net (code "10") (name "BUTTONS") (class "Default")
      (node (ref "CN8") (pin "1") (pinfunction "1_1") (pintype "unspecified"))
      (node (ref "R38") (pin "1") (pinfunction "1_1") (pintype "input"))
      (node (ref "R39") (pin "1") (pinfunction "1_1") (pintype "input"))
      (node (ref "R40") (pin "1") (pinfunction "1_1") (pintype "input"))
      (node (ref "R41") (pin "1") (pinfunction "1_1") (pintype "input"))
      (node (ref "R42") (pin "1") (pinfunction "1_1") (pintype "input"))
      (node (ref "R43") (pin "1") (pinfunction "1_1") (pintype "input"))
      (node (ref "R44") (pin "1") (pinfunction "1_1") (pintype "input"))
      (node (ref "R45") (pin "1") (pinfunction "1_1") (pintype "input"))
      (node (ref "R46") (pin "1") (pinfunction "1_1") (pintype "input"))
      (node (ref "R47") (pin "1") (pinfunction "1_1") (pintype "input"))
      (node (ref "U16") (pin "21") (pinfunction "A2_21") (pintype "unspecified"))
    )
    (net (code "11") (name "DAC_OUT_L") (class "Default")
      (node (ref "C110") (pin "1") (pinfunction "1_1") (pintype "input"))
      (node (ref "C19") (pin "2") (pinfunction "2_2") (pintype "input"))
      (node (ref "R16") (pin "1") (pinfunction "1_1") (pintype "input"))
      (node (ref "R2") (pin "2") (pinfunction "2_2") (pintype "input"))
      (node (ref "R34") (pin "1") (pinfunction "1_1") (pintype "input"))
    )
    (net (code "12") (name "DAC_OUT_R") (class "Default")
      (node (ref "C106") (pin "1") (pinfunction "1_1") (pintype "input"))
      (node (ref "C18") (pin "1") (pinfunction "1_1") (pintype "input"))
      (node (ref "R1") (pin "2") (pinfunction "2_2") (pintype "input"))
      (node (ref "R11") (pin "1") (pinfunction "1_1") (pintype "input"))
      (node (ref "R33") (pin "1") (pinfunction "1_1") (pintype "input"))
    )
    (net (code "13") (name "DISP_BOOT_SCL") (class "Default")
      (node (ref "CN29") (pin "2") (pinfunction "2_2") (pintype "unspecified"))
      (node (ref "CN32") (pin "4") (pinfunction "4_4") (pintype "unspecified"))
      (node (ref "CN36") (pin "4") (pinfunction "4_4") (pintype "unspecified"))
      (node (ref "R73") (pin "2") (pinfunction "2_2") (pintype "input"))
      (node (ref "U16") (pin "22") (pinfunction "A3_22") (pintype "unspecified"))
    )
    (net (code "14") (name "DISP_RST") (class "Default")
      (node (ref "CN29") (pin "1") (pinfunction "1_1") (pintype "unspecified"))
      (node (ref "U16") (pin "9") (pinfunction "D6_9") (pintype "unspecified"))
    )
    (net (code "15") (name "DISP_RX") (class "Default")
      (node (ref "CN22") (pin "1") (pinfunction "1_1") (pintype "unspecified"))
      (node (ref "U16") (pin "2") (pinfunction "RX1_2") (pintype "unspecified"))
    )
    (net (code "16") (name "DISP_TX") (class "Default")
      (node (ref "CN22") (pin "3") (pinfunction "3_3") (pintype "unspecified"))
      (node (ref "U16") (pin "1") (pinfunction "TX1_1") (pintype "unspecified"))
    )
    (net (code "17") (name "ENC1_A") (class "Default")
      (node (ref "CN30") (pin "4") (pinfunction "4_4") (pintype "unspecified"))
      (node (ref "R48") (pin "2") (pinfunction "2_2") (pintype "input"))
      (node (ref "U16") (pin "5") (pinfunction "D2_5") (pintype "unspecified"))
    )
    (net (code "18") (name "ENC1_B") (class "Default")
      (node (ref "CN30") (pin "3") (pinfunction "3_3") (pintype "unspecified"))
      (node (ref "R49") (pin "2") (pinfunction "2_2") (pintype "input"))
      (node (ref "U16") (pin "6") (pinfunction "D3_6") (pintype "unspecified"))
    )
    (net (code "19") (name "ENC2_A") (class "Default")
      (node (ref "CN31") (pin "4") (pinfunction "4_4") (pintype "unspecified"))
      (node (ref "R54") (pin "2") (pinfunction "2_2") (pintype "input"))
      (node (ref "U16") (pin "7") (pinfunction "D4_7") (pintype "unspecified"))
    )
    (net (code "20") (name "ENC2_B") (class "Default")
      (node (ref "CN31") (pin "3") (pinfunction "3_3") (pintype "unspecified"))
      (node (ref "R55") (pin "2") (pinfunction "2_2") (pintype "input"))
      (node (ref "U16") (pin "8") (pinfunction "D5_8") (pintype "unspecified"))
    )
    (net (code "21") (name "GND") (class "Default")
      (node (ref "C102") (pin "1") (pinfunction "1_1") (pintype "unspecified"))
      (node (ref "C103") (pin "2") (pinfunction "2_2") (pintype "unspecified"))
      (node (ref "C104") (pin "2") (pinfunction "2_2") (pintype "unspecified"))
      (node (ref "C105") (pin "1") (pinfunction "1_1") (pintype "unspecified"))
      (node (ref "C12") (pin "1") (pinfunction "1_1") (pintype "unspecified"))
      (node (ref "C14") (pin "2") (pinfunction "2_2") (pintype "unspecified"))
      (node (ref "C15") (pin "1") (pinfunction "1_1") (pintype "input"))
      (node (ref "C18") (pin "2") (pinfunction "2_2") (pintype "input"))
      (node (ref "C19") (pin "1") (pinfunction "1_1") (pintype "input"))
      (node (ref "C21") (pin "1") (pinfunction "1_1") (pintype "input"))
      (node (ref "C22") (pin "2") (pinfunction "2_2") (pintype "input"))
      (node (ref "C23") (pin "1") (pinfunction "1_1") (pintype "input"))
      (node (ref "C24") (pin "2") (pinfunction "2_2") (pintype "input"))
      (node (ref "C25") (pin "1") (pinfunction "1_1") (pintype "input"))
      (node (ref "C26") (pin "2") (pinfunction "2_2") (pintype "unspecified"))
      (node (ref "C27") (pin "2") (pinfunction "2_2") (pintype "input"))
      (node (ref "C28") (pin "2") (pinfunction "2_2") (pintype "input"))
      (node (ref "C29") (pin "2") (pinfunction "2_2") (pintype "unspecified"))
      (node (ref "C30") (pin "2") (pinfunction "2_2") (pintype "unspecified"))
      (node (ref "C32") (pin "2") (pinfunction "2_2") (pintype "unspecified"))
      (node (ref "C34") (pin "2") (pinfunction "2_2") (pintype "unspecified"))
      (node (ref "C37") (pin "2") (pinfunction "2_2") (pintype "input"))
      (node (ref "C39") (pin "2") (pinfunction "2_2") (pintype "unspecified"))
      (node (ref "C40") (pin "2") (pinfunction "2_2") (pintype "unspecified"))
      (node (ref "C41") (pin "2") (pinfunction "2_2") (pintype "input"))
      (node (ref "C42") (pin "1") (pinfunction "1_1") (pintype "unspecified"))
      (node (ref "C43") (pin "1") (pinfunction "1_1") (pintype "input"))
      (node (ref "C44") (pin "1") (pinfunction "1_1") (pintype "input"))
      (node (ref "C46") (pin "2") (pinfunction "2_2") (pintype "input"))
      (node (ref "C47") (pin "2") (pinfunction "2_2") (pintype "unspecified"))
      (node (ref "C48") (pin "1") (pinfunction "1_1") (pintype "input"))
      (node (ref "C50") (pin "2") (pinfunction "2_2") (pintype "input"))
      (node (ref "C51") (pin "2") (pinfunction "2_2") (pintype "unspecified"))
      (node (ref "C52") (pin "1") (pinfunction "1_1") (pintype "input"))
      (node (ref "C59") (pin "2") (pinfunction "2_2") (pintype "unspecified"))
      (node (ref "C63") (pin "2") (pinfunction "2_2") (pintype "unspecified"))
      (node (ref "C65") (pin "2") (pinfunction "2_2") (pintype "unspecified"))
      (node (ref "C68") (pin "2") (pinfunction "2_2") (pintype "unspecified"))
      (node (ref "C69") (pin "1") (pinfunction "1_1") (pintype "input"))
      (node (ref "C7") (pin "1") (pinfunction "1_1") (pintype "unspecified"))
      (node (ref "C71") (pin "1") (pinfunction "1_1") (pintype "unspecified"))
      (node (ref "C72") (pin "1") (pinfunction "1_1") (pintype "unspecified"))
      (node (ref "C73") (pin "2") (pinfunction "2_2") (pintype "unspecified"))
      (node (ref "C74") (pin "2") (pinfunction "2_2") (pintype "unspecified"))
      (node (ref "C75") (pin "2") (pinfunction "2_2") (pintype "input"))
      (node (ref "C8") (pin "2") (pinfunction "2_2") (pintype "unspecified"))
      (node (ref "C80") (pin "2") (pinfunction "2_2") (pintype "unspecified"))
      (node (ref "C82") (pin "2") (pinfunction "2_2") (pintype "unspecified"))
      (node (ref "C84") (pin "2") (pinfunction "2_2") (pintype "input"))
      (node (ref "C85") (pin "2") (pinfunction "2_2") (pintype "input"))
      (node (ref "C86") (pin "2") (pinfunction "2_2") (pintype "input"))
      (node (ref "C87") (pin "2") (pinfunction "2_2") (pintype "unspecified"))
      (node (ref "C88") (pin "1") (pinfunction "1_1") (pintype "unspecified"))
      (node (ref "C89") (pin "1") (pinfunction "1_1") (pintype "unspecified"))
      (node (ref "C90") (pin "2") (pinfunction "2_2") (pintype "unspecified"))
      (node (ref "C91") (pin "2") (pinfunction "2_2") (pintype "unspecified"))
      (node (ref "C92") (pin "1") (pinfunction "1_1") (pintype "unspecified"))
      (node (ref "CARD1") (pin "10") (pinfunction "GND_10") (pintype "input"))
      (node (ref "CARD1") (pin "11") (pinfunction "GND_11") (pintype "input"))
      (node (ref "CARD1") (pin "12") (pinfunction "GND_12") (pintype "input"))
      (node (ref "CARD1") (pin "13") (pinfunction "GND_13") (pintype "input"))
      (node (ref "CARD1") (pin "6") (pinfunction "VSS_6") (pintype "input"))
      (node (ref "CN10") (pin "2") (pinfunction "2_2") (pintype "unspecified"))
      (node (ref "CN11") (pin "2") (pinfunction "2_2") (pintype "unspecified"))
      (node (ref "CN12") (pin "2") (pinfunction "2_2") (pintype "unspecified"))
      (node (ref "CN13") (pin "2") (pinfunction "2_2") (pintype "unspecified"))
      (node (ref "CN14") (pin "2") (pinfunction "2_2") (pintype "unspecified"))
      (node (ref "CN15") (pin "2") (pinfunction "2_2") (pintype "unspecified"))
      (node (ref "CN16") (pin "2") (pinfunction "2_2") (pintype "unspecified"))
      (node (ref "CN17") (pin "2") (pinfunction "2_2") (pintype "unspecified"))
      (node (ref "CN22") (pin "2") (pinfunction "2_2") (pintype "unspecified"))
      (node (ref "CN25") (pin "1") (pinfunction "1_1") (pintype "unspecified"))
      (node (ref "CN26") (pin "1") (pinfunction "1_1") (pintype "unspecified"))
      (node (ref "CN3") (pin "2") (pinfunction "2_2") (pintype "unspecified"))
      (node (ref "CN30") (pin "1") (pinfunction "1_1") (pintype "unspecified"))
      (node (ref "CN31") (pin "1") (pinfunction "1_1") (pintype "unspecified"))
      (node (ref "CN32") (pin "1") (pinfunction "1_1") (pintype "unspecified"))
      (node (ref "CN34") (pin "1") (pinfunction "1_1") (pintype "unspecified"))
      (node (ref "CN35") (pin "1") (pinfunction "1_1") (pintype "unspecified"))
      (node (ref "CN36") (pin "1") (pinfunction "1_1") (pintype "unspecified"))
      (node (ref "CN4") (pin "1") (pinfunction "1_1") (pintype "unspecified"))
      (node (ref "CN5") (pin "1") (pinfunction "1_1") (pintype "unspecified"))
      (node (ref "CN7") (pin "2") (pinfunction "2_2") (pintype "unspecified"))
      (node (ref "CN8") (pin "2") (pinfunction "2_2") (pintype "unspecified"))
      (node (ref "CN9") (pin "2") (pinfunction "2_2") (pintype "unspecified"))
      (node (ref "D4") (pin "2") (pinfunction "A_2") (pintype "unspecified"))
      (node (ref "D5") (pin "2") (pinfunction "A_2") (pintype "unspecified"))
      (node (ref "D6") (pin "1") (pinfunction "1_1") (pintype "unspecified"))
      (node (ref "R11") (pin "2") (pinfunction "2_2") (pintype "input"))
      (node (ref "R16") (pin "2") (pinfunction "2_2") (pintype "input"))
      (node (ref "R19") (pin "2") (pinfunction "2_2") (pintype "input"))
      (node (ref "R20") (pin "1") (pinfunction "1_1") (pintype "input"))
      (node (ref "R24") (pin "2") (pinfunction "2_2") (pintype "input"))
      (node (ref "R25") (pin "1") (pinfunction "1_1") (pintype "input"))
      (node (ref "R36") (pin "1") (pinfunction "1_1") (pintype "input"))
      (node (ref "R4") (pin "1") (pinfunction "1_1") (pintype "input"))
      (node (ref "R52") (pin "2") (pinfunction "2_2") (pintype "input"))
      (node (ref "R53") (pin "2") (pinfunction "2_2") (pintype "input"))
      (node (ref "R64") (pin "1") (pinfunction "1_1") (pintype "input"))
      (node (ref "R67") (pin "2") (pinfunction "2_2") (pintype "input"))
      (node (ref "U1") (pin "10") (pinfunction "DEMP_10") (pintype "input"))
      (node (ref "U1") (pin "11") (pinfunction "FLT_11") (pintype "input"))
      (node (ref "U1") (pin "16") (pinfunction "FMT_16") (pintype "input"))
      (node (ref "U1") (pin "19") (pinfunction "DGND_19") (pintype "input"))
      (node (ref "U1") (pin "3") (pinfunction "CPGND_3") (pintype "input"))
      (node (ref "U1") (pin "9") (pinfunction "AGND_9") (pintype "input"))
      (node (ref "U10") (pin "1") (pinfunction "1_1") (pintype "unspecified"))
      (node (ref "U12") (pin "1") (pinfunction "GND_1") (pintype "unspecified"))
      (node (ref "U12") (pin "7") (pinfunction "PGND_7") (pintype "unspecified"))
      (node (ref "U12") (pin "9") (pinfunction "EP_9") (pintype "unspecified"))
      (node (ref "U14") (pin "2") (pinfunction "GND_2") (pintype "unspecified"))
      (node (ref "U15") (pin "5") (pinfunction "GND_5") (pintype "unspecified"))
      (node (ref "U16") (pin "29") (pinfunction "GND_29") (pintype "unspecified"))
      (node (ref "U16") (pin "31") (pinfunction "EH_31") (pintype "unspecified"))
      (node (ref "U16") (pin "32") (pinfunction "EH_32") (pintype "unspecified"))
      (node (ref "U16") (pin "33") (pinfunction "EH_33") (pintype "unspecified"))
      (node (ref "U16") (pin "34") (pinfunction "EH_34") (pintype "unspecified"))
      (node (ref "U16") (pin "4") (pinfunction "GND_4") (pintype "unspecified"))
      (node (ref "U17") (pin "2") (pinfunction "GND_2") (pintype "unspecified"))
      (node (ref "U2") (pin "6") (pinfunction "V-_6") (pintype "unspecified"))
      (node (ref "U3") (pin "2") (pinfunction "V-_2") (pintype "unspecified"))
      (node (ref "U6") (pin "6") (pinfunction "V-_6") (pintype "unspecified"))
      (node (ref "U7") (pin "2") (pinfunction "2_2") (pintype "unspecified"))
      (node (ref "U8") (pin "1") (pinfunction "1_1") (pintype "unspecified"))
      (node (ref "U9") (pin "2") (pinfunction "2_2") (pintype "unspecified"))
    )
    (net (code "22") (name "LRCK") (class "Default")
      (node (ref "CN33") (pin "4") (pinfunction "4_4") (pintype "unspecified"))
      (node (ref "R61") (pin "1") (pinfunction "1_1") (pintype "input"))
      (node (ref "U1") (pin "15") (pinfunction "LRCK_15") (pintype "input"))
    )
    (net (code "23") (name "MIDI+") (class "Default")
      (node (ref "CN6") (pin "3") (pinfunction "3_3") (pintype "unspecified"))
      (node (ref "D3") (pin "2") (pinfunction "2_2") (pintype "unspecified"))
      (node (ref "L12") (pin "1") (pinfunction "1_1") (pintype "unspecified"))
    )
    (net (code "24") (name "MIDI-") (class "Default")
      (node (ref "CN6") (pin "1") (pinfunction "1_1") (pintype "unspecified"))
      (node (ref "D2") (pin "2") (pinfunction "2_2") (pintype "unspecified"))
      (node (ref "L13") (pin "1") (pinfunction "1_1") (pintype "unspecified"))
    )
    (net (code "25") (name "MIDI-GND") (class "Default")
      (node (ref "C77") (pin "1") (pinfunction "1_1") (pintype "input"))
      (node (ref "D2") (pin "1") (pinfunction "1_1") (pintype "unspecified"))
      (node (ref "D3") (pin "1") (pinfunction "1_1") (pintype "unspecified"))
      (node (ref "R32") (pin "1") (pinfunction "1_1") (pintype "input"))
    )
    (net (code "26") (name "MIDI-SHLD") (class "Default")
      (node (ref "C77") (pin "2") (pinfunction "2_2") (pintype "input"))
      (node (ref "CN6") (pin "2") (pinfunction "2_2") (pintype "unspecified"))
      (node (ref "R32") (pin "2") (pinfunction "2_2") (pintype "input"))
    )
    (net (code "27") (name "MIDI_RX") (class "Default")
      (node (ref "R29") (pin "1") (pinfunction "1_1") (pintype "input"))
      (node (ref "U15") (pin "6") (pinfunction "VOUT_6") (pintype "unspecified"))
      (node (ref "U16") (pin "12") (pinfunction "D9_12") (pintype "unspecified"))
    )
    (net (code "28") (name "MOT_1") (class "Default")
      (node (ref "U12") (pin "3") (pinfunction "IN1_3") (pintype "unspecified"))
      (node (ref "U16") (pin "10") (pinfunction "D7_10") (pintype "unspecified"))
    )
    (net (code "29") (name "MOT_2") (class "Default")
      (node (ref "U12") (pin "2") (pinfunction "IN2_2") (pintype "unspecified"))
      (node (ref "U16") (pin "11") (pinfunction "D8_11") (pintype "unspecified"))
    )
    (net (code "30") (name "Net-(C34-Pad1)") (class "Default")
      (node (ref "C34") (pin "1") (pinfunction "1_1") (pintype "unspecified"))
      (node (ref "L10") (pin "1") (pinfunction "1_1") (pintype "unspecified"))
      (node (ref "L11") (pin "1") (pinfunction "1_1") (pintype "unspecified"))
    )
    (net (code "31") (name "Net-(C63-Pad1)") (class "Default")
      (node (ref "C63") (pin "1") (pinfunction "1_1") (pintype "unspecified"))
      (node (ref "L6") (pin "1") (pinfunction "1_1") (pintype "unspecified"))
      (node (ref "L7") (pin "2") (pinfunction "2_2") (pintype "unspecified"))
    )
    (net (code "32") (name "Net-(C72-Pad2)") (class "Default")
      (node (ref "C72") (pin "2") (pinfunction "2_2") (pintype "unspecified"))
      (node (ref "L2") (pin "2") (pinfunction "2_2") (pintype "unspecified"))
      (node (ref "L9") (pin "2") (pinfunction "2_2") (pintype "unspecified"))
    )
    (net (code "33") (name "Net-(C74-Pad1)") (class "Default")
      (node (ref "C74") (pin "1") (pinfunction "1_1") (pintype "unspecified"))
      (node (ref "L1") (pin "2") (pinfunction "2_2") (pintype "unspecified"))
      (node (ref "L10") (pin "2") (pinfunction "2_2") (pintype "unspecified"))
    )
    (net (code "34") (name "Net-(C106-Pad2)") (class "Default")
      (node (ref "C106") (pin "2") (pinfunction "2_2") (pintype "input"))
      (node (ref "R6") (pin "2") (pinfunction "2_2") (pintype "input"))
    )
    (net (code "35") (name "Net-(C107-Pad1)") (class "Default")
      (node (ref "C107") (pin "1") (pinfunction "1_1") (pintype "input"))
      (node (ref "R18") (pin "2") (pinfunction "2_2") (pintype "input"))
    )
    (net (code "36") (name "Net-(C107-Pad2)") (class "Default")
      (node (ref "C107") (pin "2") (pinfunction "2_2") (pintype "input"))
      (node (ref "CN4") (pin "2") (pinfunction "2_2") (pintype "unspecified"))
      (node (ref "R20") (pin "2") (pinfunction "2_2") (pintype "input"))
      (node (ref "U8") (pin "2") (pinfunction "2_2") (pintype "unspecified"))
    )
    (net (code "37") (name "Net-(C108-Pad1)") (class "Default")
      (node (ref "C108") (pin "1") (pinfunction "1_1") (pintype "input"))
      (node (ref "R34") (pin "2") (pinfunction "2_2") (pintype "input"))
    )
    (net (code "38") (name "Net-(C108-Pad2)") (class "Default")
      (node (ref "C108") (pin "2") (pinfunction "2_2") (pintype "input"))
      (node (ref "CN3") (pin "1") (pinfunction "1_1") (pintype "unspecified"))
    )
    (net (code "39") (name "Net-(C109-Pad1)") (class "Default")
      (node (ref "C109") (pin "1") (pinfunction "1_1") (pintype "input"))
      (node (ref "R33") (pin "2") (pinfunction "2_2") (pintype "input"))
    )
    (net (code "40") (name "Net-(C109-Pad2)") (class "Default")
      (node (ref "C109") (pin "2") (pinfunction "2_2") (pintype "input"))
      (node (ref "CN3") (pin "3") (pinfunction "3_3") (pintype "unspecified"))
    )
    (net (code "41") (name "Net-(C110-Pad2)") (class "Default")
      (node (ref "C110") (pin "2") (pinfunction "2_2") (pintype "input"))
      (node (ref "R17") (pin "2") (pinfunction "2_2") (pintype "input"))
    )
    (net (code "42") (name "Net-(C111-Pad1)") (class "Default")
      (node (ref "C111") (pin "1") (pinfunction "1_1") (pintype "input"))
      (node (ref "R8") (pin "2") (pinfunction "2_2") (pintype "input"))
    )
    (net (code "43") (name "Net-(C111-Pad2)") (class "Default")
      (node (ref "C111") (pin "2") (pinfunction "2_2") (pintype "input"))
      (node (ref "CN4") (pin "3") (pinfunction "3_3") (pintype "unspecified"))
      (node (ref "R19") (pin "1") (pinfunction "1_1") (pintype "input"))
      (node (ref "U7") (pin "1") (pinfunction "1_1") (pintype "unspecified"))
    )
    (net (code "44") (name "Net-(C112-Pad1)") (class "Default")
      (node (ref "C112") (pin "1") (pinfunction "1_1") (pintype "input"))
      (node (ref "R22") (pin "2") (pinfunction "2_2") (pintype "input"))
    )
    (net (code "45") (name "Net-(C112-Pad2)") (class "Default")
      (node (ref "C112") (pin "2") (pinfunction "2_2") (pintype "input"))
      (node (ref "CN5") (pin "3") (pinfunction "3_3") (pintype "unspecified"))
      (node (ref "R24") (pin "1") (pinfunction "1_1") (pintype "input"))
      (node (ref "U9") (pin "1") (pinfunction "1_1") (pintype "unspecified"))
    )
    (net (code "46") (name "Net-(C113-Pad1)") (class "Default")
      (node (ref "C113") (pin "1") (pinfunction "1_1") (pintype "input"))
      (node (ref "R23") (pin "2") (pinfunction "2_2") (pintype "input"))
    )
    (net (code "47") (name "Net-(C113-Pad2)") (class "Default")
      (node (ref "C113") (pin "2") (pinfunction "2_2") (pintype "input"))
      (node (ref "CN5") (pin "2") (pinfunction "2_2") (pintype "unspecified"))
      (node (ref "R25") (pin "2") (pinfunction "2_2") (pintype "input"))
      (node (ref "U10") (pin "2") (pinfunction "2_2") (pintype "unspecified"))
    )
    (net (code "48") (name "Net-(CARD1-DAT0(D0))") (class "Default")
      (node (ref "CARD1") (pin "7") (pinfunction "DAT0(D0)_7") (pintype "bidirectional"))
      (node (ref "R70") (pin "2") (pinfunction "2_2") (pintype "input"))
    )
    (net (code "49") (name "Net-(CN7-Pad1)") (class "Default")
      (node (ref "CN7") (pin "1") (pinfunction "1_1") (pintype "unspecified"))
      (node (ref "F1") (pin "1") (pinfunction "1_1") (pintype "unspecified"))
    )
    (net (code "50") (name "Net-(CN9-Pad1)") (class "Default")
      (node (ref "CN9") (pin "1") (pinfunction "1_1") (pintype "unspecified"))
      (node (ref "R39") (pin "2") (pinfunction "2_2") (pintype "input"))
    )
    (net (code "51") (name "Net-(CN10-Pad1)") (class "Default")
      (node (ref "CN10") (pin "1") (pinfunction "1_1") (pintype "unspecified"))
      (node (ref "R40") (pin "2") (pinfunction "2_2") (pintype "input"))
    )
    (net (code "52") (name "Net-(CN11-Pad1)") (class "Default")
      (node (ref "CN11") (pin "1") (pinfunction "1_1") (pintype "unspecified"))
      (node (ref "R47") (pin "2") (pinfunction "2_2") (pintype "input"))
    )
    (net (code "53") (name "Net-(CN12-Pad1)") (class "Default")
      (node (ref "CN12") (pin "1") (pinfunction "1_1") (pintype "unspecified"))
      (node (ref "R41") (pin "2") (pinfunction "2_2") (pintype "input"))
    )
    (net (code "54") (name "Net-(CN13-Pad1)") (class "Default")
      (node (ref "CN13") (pin "1") (pinfunction "1_1") (pintype "unspecified"))
      (node (ref "R42") (pin "2") (pinfunction "2_2") (pintype "input"))
    )
    (net (code "55") (name "Net-(CN14-Pad1)") (class "Default")
      (node (ref "CN14") (pin "1") (pinfunction "1_1") (pintype "unspecified"))
      (node (ref "R43") (pin "2") (pinfunction "2_2") (pintype "input"))
    )
    (net (code "56") (name "Net-(CN15-Pad1)") (class "Default")
      (node (ref "CN15") (pin "1") (pinfunction "1_1") (pintype "unspecified"))
      (node (ref "R44") (pin "2") (pinfunction "2_2") (pintype "input"))
    )
    (net (code "57") (name "Net-(CN16-Pad1)") (class "Default")
      (node (ref "CN16") (pin "1") (pinfunction "1_1") (pintype "unspecified"))
      (node (ref "R45") (pin "2") (pinfunction "2_2") (pintype "input"))
    )
    (net (code "58") (name "Net-(CN17-Pad1)") (class "Default")
      (node (ref "CN17") (pin "1") (pinfunction "1_1") (pintype "unspecified"))
      (node (ref "R46") (pin "2") (pinfunction "2_2") (pintype "input"))
    )
    (net (code "59") (name "Net-(D1-A)") (class "Default")
      (node (ref "D1") (pin "2") (pinfunction "A_2") (pintype "unspecified"))
      (node (ref "L13") (pin "2") (pinfunction "2_2") (pintype "unspecified"))
      (node (ref "U15") (pin "3") (pinfunction "CAT_3") (pintype "unspecified"))
    )
    (net (code "60") (name "Net-(D1-K)") (class "Default")
      (node (ref "D1") (pin "1") (pinfunction "K_1") (pintype "unspecified"))
      (node (ref "R31") (pin "2") (pinfunction "2_2") (pintype "input"))
      (node (ref "U15") (pin "2") (pinfunction "AN_2") (pintype "unspecified"))
    )
    (net (code "61") (name "Net-(D4-K)") (class "Default")
      (node (ref "C81") (pin "1") (pinfunction "1_1") (pintype "input"))
      (node (ref "D4") (pin "1") (pinfunction "K_1") (pintype "unspecified"))
      (node (ref "L14") (pin "1") (pinfunction "1_1") (pintype "unspecified"))
      (node (ref "U17") (pin "6") (pinfunction "SW_6") (pintype "unspecified"))
    )
    (net (code "62") (name "Net-(D7-K)") (class "Default")
      (node (ref "C88") (pin "2") (pinfunction "2_2") (pintype "unspecified"))
      (node (ref "C89") (pin "2") (pinfunction "2_2") (pintype "unspecified"))
      (node (ref "D7") (pin "1") (pinfunction "K_1") (pintype "unspecified"))
      (node (ref "U16") (pin "30") (pinfunction "VIN_30") (pintype "unspecified"))
    )
    (net (code "63") (name "Net-(L12-Pad2)") (class "Default")
      (node (ref "L12") (pin "2") (pinfunction "2_2") (pintype "unspecified"))
      (node (ref "R31") (pin "1") (pinfunction "1_1") (pintype "input"))
    )
    (net (code "64") (name "Net-(U1-CAPM)") (class "Default")
      (node (ref "C16") (pin "2") (pinfunction "2_2") (pintype "input"))
      (node (ref "U1") (pin "4") (pinfunction "CAPM_4") (pintype "input"))
    )
    (net (code "65") (name "Net-(U1-CAPP)") (class "Default")
      (node (ref "C16") (pin "1") (pinfunction "1_1") (pintype "input"))
      (node (ref "U1") (pin "2") (pinfunction "CAPP_2") (pintype "input"))
    )
    (net (code "66") (name "Net-(U1-LDOO)") (class "Default")
      (node (ref "C21") (pin "2") (pinfunction "2_2") (pintype "input"))
      (node (ref "C7") (pin "2") (pinfunction "2_2") (pintype "unspecified"))
      (node (ref "U1") (pin "18") (pinfunction "LDOO_18") (pintype "input"))
    )
    (net (code "67") (name "Net-(U1-OUTL)") (class "Default")
      (node (ref "R2") (pin "1") (pinfunction "1_1") (pintype "input"))
      (node (ref "U1") (pin "6") (pinfunction "OUTL_6") (pintype "input"))
    )
    (net (code "68") (name "Net-(U1-OUTR)") (class "Default")
      (node (ref "R1") (pin "1") (pinfunction "1_1") (pintype "input"))
      (node (ref "U1") (pin "7") (pinfunction "OUTR_7") (pintype "input"))
    )
    (net (code "69") (name "Net-(U1-VNEG)") (class "Default")
      (node (ref "C15") (pin "2") (pinfunction "2_2") (pintype "input"))
      (node (ref "C23") (pin "2") (pinfunction "2_2") (pintype "input"))
      (node (ref "U1") (pin "5") (pinfunction "VNEG_5") (pintype "input"))
    )
    (net (code "70") (name "Net-(U2-Enable)") (class "Default")
      (node (ref "R5") (pin "1") (pinfunction "1_1") (pintype "input"))
      (node (ref "U2") (pin "7") (pinfunction "Enable_7") (pintype "unspecified"))
    )
    (net (code "71") (name "Net-(U2-VIN+)") (class "Default")
      (node (ref "R6") (pin "1") (pinfunction "1_1") (pintype "input"))
      (node (ref "R7") (pin "1") (pinfunction "1_1") (pintype "input"))
      (node (ref "R75") (pin "1") (pinfunction "1_1") (pintype "input"))
      (node (ref "U2") (pin "8") (pinfunction "VIN+_8") (pintype "unspecified"))
    )
    (net (code "72") (name "Net-(U2-VIN-)") (class "Default")
      (node (ref "R10") (pin "1") (pinfunction "1_1") (pintype "input"))
      (node (ref "R9") (pin "2") (pinfunction "2_2") (pintype "input"))
      (node (ref "U2") (pin "1") (pinfunction "VIN-_1") (pintype "unspecified"))
    )
    (net (code "73") (name "Net-(U3-IN+)") (class "Default")
      (node (ref "C69") (pin "2") (pinfunction "2_2") (pintype "input"))
      (node (ref "R3") (pin "1") (pinfunction "1_1") (pintype "input"))
      (node (ref "R4") (pin "2") (pinfunction "2_2") (pintype "input"))
      (node (ref "U3") (pin "3") (pinfunction "IN+_3") (pintype "unspecified"))
    )
    (net (code "74") (name "Net-(U3-IN-)") (class "Default")
      (node (ref "R21") (pin "1") (pinfunction "1_1") (pintype "input"))
      (node (ref "U3") (pin "1") (pinfunction "OUT_1") (pintype "output"))
      (node (ref "U3") (pin "4") (pinfunction "IN-_4") (pintype "unspecified"))
    )
    (net (code "75") (name "Net-(U6-Enable)") (class "Default")
      (node (ref "R12") (pin "1") (pinfunction "1_1") (pintype "input"))
      (node (ref "U6") (pin "7") (pinfunction "Enable_7") (pintype "unspecified"))
    )
    (net (code "76") (name "Net-(U6-VIN+)") (class "Default")
      (node (ref "R13") (pin "1") (pinfunction "1_1") (pintype "input"))
      (node (ref "R17") (pin "1") (pinfunction "1_1") (pintype "input"))
      (node (ref "R74") (pin "2") (pinfunction "2_2") (pintype "input"))
      (node (ref "U6") (pin "8") (pinfunction "VIN+_8") (pintype "unspecified"))
    )
    (net (code "77") (name "Net-(U6-VIN-)") (class "Default")
      (node (ref "R14") (pin "2") (pinfunction "2_2") (pintype "input"))
      (node (ref "R15") (pin "1") (pinfunction "1_1") (pintype "input"))
      (node (ref "U6") (pin "1") (pinfunction "VIN-_1") (pintype "unspecified"))
    )
    (net (code "78") (name "Net-(U12-ILIM)") (class "Default")
      (node (ref "R64") (pin "2") (pinfunction "2_2") (pintype "input"))
      (node (ref "U12") (pin "4") (pinfunction "ILIM_4") (pintype "unspecified"))
    )
    (net (code "79") (name "Net-(U12-OUT1)") (class "Default")
      (node (ref "CN24") (pin "1") (pinfunction "1_1") (pintype "unspecified"))
      (node (ref "U12") (pin "6") (pinfunction "OUT1_6") (pintype "unspecified"))
    )
    (net (code "80") (name "Net-(U12-OUT2)") (class "Default")
      (node (ref "CN24") (pin "2") (pinfunction "2_2") (pintype "unspecified"))
      (node (ref "U12") (pin "8") (pinfunction "OUT2_8") (pintype "unspecified"))
    )
    (net (code "81") (name "Net-(U12-VM)") (class "Default")
      (node (ref "C37") (pin "1") (pinfunction "1_1") (pintype "input"))
      (node (ref "R65") (pin "1") (pinfunction "1_1") (pintype "input"))
      (node (ref "R66") (pin "1") (pinfunction "1_1") (pintype "input"))
      (node (ref "U12") (pin "5") (pinfunction "VM_5") (pintype "unspecified"))
    )
    (net (code "82") (name "Net-(U16-A4)") (class "Default")
      (node (ref "R60") (pin "2") (pinfunction "2_2") (pintype "input"))
      (node (ref "U16") (pin "23") (pinfunction "A4_23") (pintype "unspecified"))
    )
    (net (code "83") (name "Net-(U16-A5)") (class "Default")
      (node (ref "R61") (pin "2") (pinfunction "2_2") (pintype "input"))
      (node (ref "U16") (pin "24") (pinfunction "A5_24") (pintype "unspecified"))
    )
    (net (code "84") (name "Net-(U16-A6)") (class "Default")
      (node (ref "R62") (pin "2") (pinfunction "2_2") (pintype "input"))
      (node (ref "U16") (pin "25") (pinfunction "A6_25") (pintype "unspecified"))
    )
    (net (code "85") (name "Net-(U16-A7)") (class "Default")
      (node (ref "R63") (pin "2") (pinfunction "2_2") (pintype "input"))
      (node (ref "U16") (pin "26") (pinfunction "A7_26") (pintype "unspecified"))
    )
    (net (code "86") (name "Net-(U16-D10)") (class "Default")
      (node (ref "R72") (pin "1") (pinfunction "1_1") (pintype "input"))
      (node (ref "U16") (pin "13") (pinfunction "D10_13") (pintype "unspecified"))
    )
    (net (code "87") (name "Net-(U16-D11)") (class "Default")
      (node (ref "R71") (pin "1") (pinfunction "1_1") (pintype "input"))
      (node (ref "U16") (pin "14") (pinfunction "D11_14") (pintype "unspecified"))
    )
    (net (code "88") (name "Net-(U16-D13)") (class "Default")
      (node (ref "R69") (pin "2") (pinfunction "2_2") (pintype "input"))
      (node (ref "U16") (pin "16") (pinfunction "D13_16") (pintype "unspecified"))
    )
    (net (code "89") (name "Net-(U17-BS)") (class "Default")
      (node (ref "C81") (pin "2") (pinfunction "2_2") (pintype "input"))
      (node (ref "U17") (pin "1") (pinfunction "BS_1") (pintype "unspecified"))
    )
    (net (code "90") (name "Net-(U17-FB)") (class "Default")
      (node (ref "R36") (pin "2") (pinfunction "2_2") (pintype "input"))
      (node (ref "R37") (pin "1") (pinfunction "1_1") (pintype "input"))
      (node (ref "U17") (pin "3") (pinfunction "FB_3") (pintype "unspecified"))
    )
    (net (code "91") (name "POTI1") (class "Default")
      (node (ref "CN20") (pin "1") (pinfunction "1_1") (pintype "unspecified"))
      (node (ref "R52") (pin "1") (pinfunction "1_1") (pintype "input"))
      (node (ref "U16") (pin "19") (pinfunction "A0_19") (pintype "unspecified"))
    )
    (net (code "92") (name "POTI2") (class "Default")
      (node (ref "CN21") (pin "1") (pinfunction "1_1") (pintype "unspecified"))
      (node (ref "R53") (pin "1") (pinfunction "1_1") (pintype "input"))
      (node (ref "U16") (pin "20") (pinfunction "A1_20") (pintype "unspecified"))
    )
    (net (code "93") (name "SCK") (class "Default")
      (node (ref "CN33") (pin "1") (pinfunction "1_1") (pintype "unspecified"))
      (node (ref "R60") (pin "1") (pinfunction "1_1") (pintype "input"))
      (node (ref "U1") (pin "12") (pinfunction "SCK_12") (pintype "input"))
    )
    (net (code "94") (name "SD_CS") (class "Default")
      (node (ref "CARD1") (pin "2") (pinfunction "CDDAT3(CS)_2") (pintype "bidirectional"))
      (node (ref "R57") (pin "2") (pinfunction "2_2") (pintype "input"))
      (node (ref "R72") (pin "2") (pinfunction "2_2") (pintype "input"))
    )
    (net (code "95") (name "SD_MISO") (class "Default")
      (node (ref "R56") (pin "2") (pinfunction "2_2") (pintype "input"))
      (node (ref "R70") (pin "1") (pinfunction "1_1") (pintype "input"))
      (node (ref "U16") (pin "15") (pinfunction "D12_15") (pintype "unspecified"))
    )
    (net (code "96") (name "SD_MOSI") (class "Default")
      (node (ref "CARD1") (pin "3") (pinfunction "CMD(DI)_3") (pintype "input"))
      (node (ref "R58") (pin "2") (pinfunction "2_2") (pintype "input"))
      (node (ref "R71") (pin "2") (pinfunction "2_2") (pintype "input"))
    )
    (net (code "97") (name "SD_SCK") (class "Default")
      (node (ref "CARD1") (pin "5") (pinfunction "CLK(SCLK)_5") (pintype "input"))
      (node (ref "R59") (pin "2") (pinfunction "2_2") (pintype "input"))
      (node (ref "R69") (pin "1") (pinfunction "1_1") (pintype "input"))
    )
    (net (code "98") (name "SERVO1") (class "Default")
      (node (ref "CN25") (pin "3") (pinfunction "3_3") (pintype "unspecified"))
      (node (ref "R67") (pin "1") (pinfunction "1_1") (pintype "input"))
      (node (ref "U16") (pin "18") (pinfunction "B0_18") (pintype "unspecified"))
    )
    (net (code "99") (name "SERVO2_SDA") (class "Default")
      (node (ref "CN26") (pin "3") (pinfunction "3_3") (pintype "unspecified"))
      (node (ref "CN32") (pin "3") (pinfunction "3_3") (pintype "unspecified"))
      (node (ref "CN36") (pin "3") (pinfunction "3_3") (pintype "unspecified"))
      (node (ref "R68") (pin "1") (pinfunction "1_1") (pintype "input"))
      (node (ref "U16") (pin "28") (pinfunction "B1_28") (pintype "unspecified"))
    )
    (net (code "100") (name "VIN") (class "Default")
      (node (ref "C80") (pin "1") (pinfunction "1_1") (pintype "unspecified"))
      (node (ref "C85") (pin "1") (pinfunction "1_1") (pintype "input"))
      (node (ref "D5") (pin "1") (pinfunction "K_1") (pintype "unspecified"))
      (node (ref "D6") (pin "2") (pinfunction "2_2") (pintype "unspecified"))
      (node (ref "F1") (pin "2") (pinfunction "2_2") (pintype "unspecified"))
      (node (ref "R65") (pin "2") (pinfunction "2_2") (pintype "input"))
      (node (ref "U17") (pin "4") (pinfunction "EN_4") (pintype "unspecified"))
      (node (ref "U17") (pin "5") (pinfunction "IN_5") (pintype "unspecified"))
    )
    (net (code "101") (name "VOUT+_L") (class "Default")
      (node (ref "R15") (pin "2") (pinfunction "2_2") (pintype "input"))
      (node (ref "R22") (pin "1") (pinfunction "1_1") (pintype "input"))
      (node (ref "U6") (pin "4") (pinfunction "VOUT+_4") (pintype "unspecified"))
    )
    (net (code "102") (name "VOUT+_R") (class "Default")
      (node (ref "R10") (pin "2") (pinfunction "2_2") (pintype "input"))
      (node (ref "R8") (pin "1") (pinfunction "1_1") (pintype "input"))
      (node (ref "U2") (pin "4") (pinfunction "VOUT+_4") (pintype "unspecified"))
    )
    (net (code "103") (name "VOUT-_L") (class "Default")
      (node (ref "R23") (pin "1") (pinfunction "1_1") (pintype "input"))
      (node (ref "R74") (pin "1") (pinfunction "1_1") (pintype "input"))
      (node (ref "U6") (pin "5") (pinfunction "VOUT-_5") (pintype "unspecified"))
    )
    (net (code "104") (name "VOUT-_R") (class "Default")
      (node (ref "R18") (pin "1") (pinfunction "1_1") (pintype "input"))
      (node (ref "R75") (pin "2") (pinfunction "2_2") (pintype "input"))
      (node (ref "U2") (pin "5") (pinfunction "VOUT-_5") (pintype "unspecified"))
    )
    (net (code "105") (name "unconnected-(CARD1-CD-Pad9)") (class "Default")
      (node (ref "CARD1") (pin "9") (pinfunction "CD_9") (pintype "input"))
    )
    (net (code "106") (name "unconnected-(CARD1-DAT1(RSV)-Pad8)") (class "Default")
      (node (ref "CARD1") (pin "8") (pinfunction "DAT1(RSV)_8") (pintype "bidirectional"))
    )
    (net (code "107") (name "unconnected-(CARD1-DAT2(RSV)-Pad1)") (class "Default")
      (node (ref "CARD1") (pin "1") (pinfunction "DAT2(RSV)_1") (pintype "bidirectional"))
    )
    (net (code "108") (name "unconnected-(U14-NC-Pad4)") (class "Default")
      (node (ref "U14") (pin "4") (pinfunction "NC_4") (pintype "unspecified"))
    )
    (net (code "109") (name "unconnected-(U15-NC-Pad1)") (class "Default")
      (node (ref "U15") (pin "1") (pinfunction "NC_1") (pintype "unspecified"))
    )
    (net (code "110") (name "unconnected-(U15-NC-Pad4)") (class "Default")
      (node (ref "U15") (pin "4") (pinfunction "NC_4") (pintype "unspecified"))
    )
    (net (code "111") (name "unconnected-(U16-RST-Pad3)") (class "Default")
      (node (ref "U16") (pin "3") (pinfunction "RST_3") (pintype "unspecified+no_connect"))
    )
    (net (code "112") (name "unconnected-(U16-VBUS-Pad27)") (class "Default")
      (node (ref "U16") (pin "27") (pinfunction "VBUS_27") (pintype "unspecified+no_connect"))
    )
  )
)
